# Tractive_System_Board_Rev4.net
KiCad netlist of a schematic drawn in EAGLE
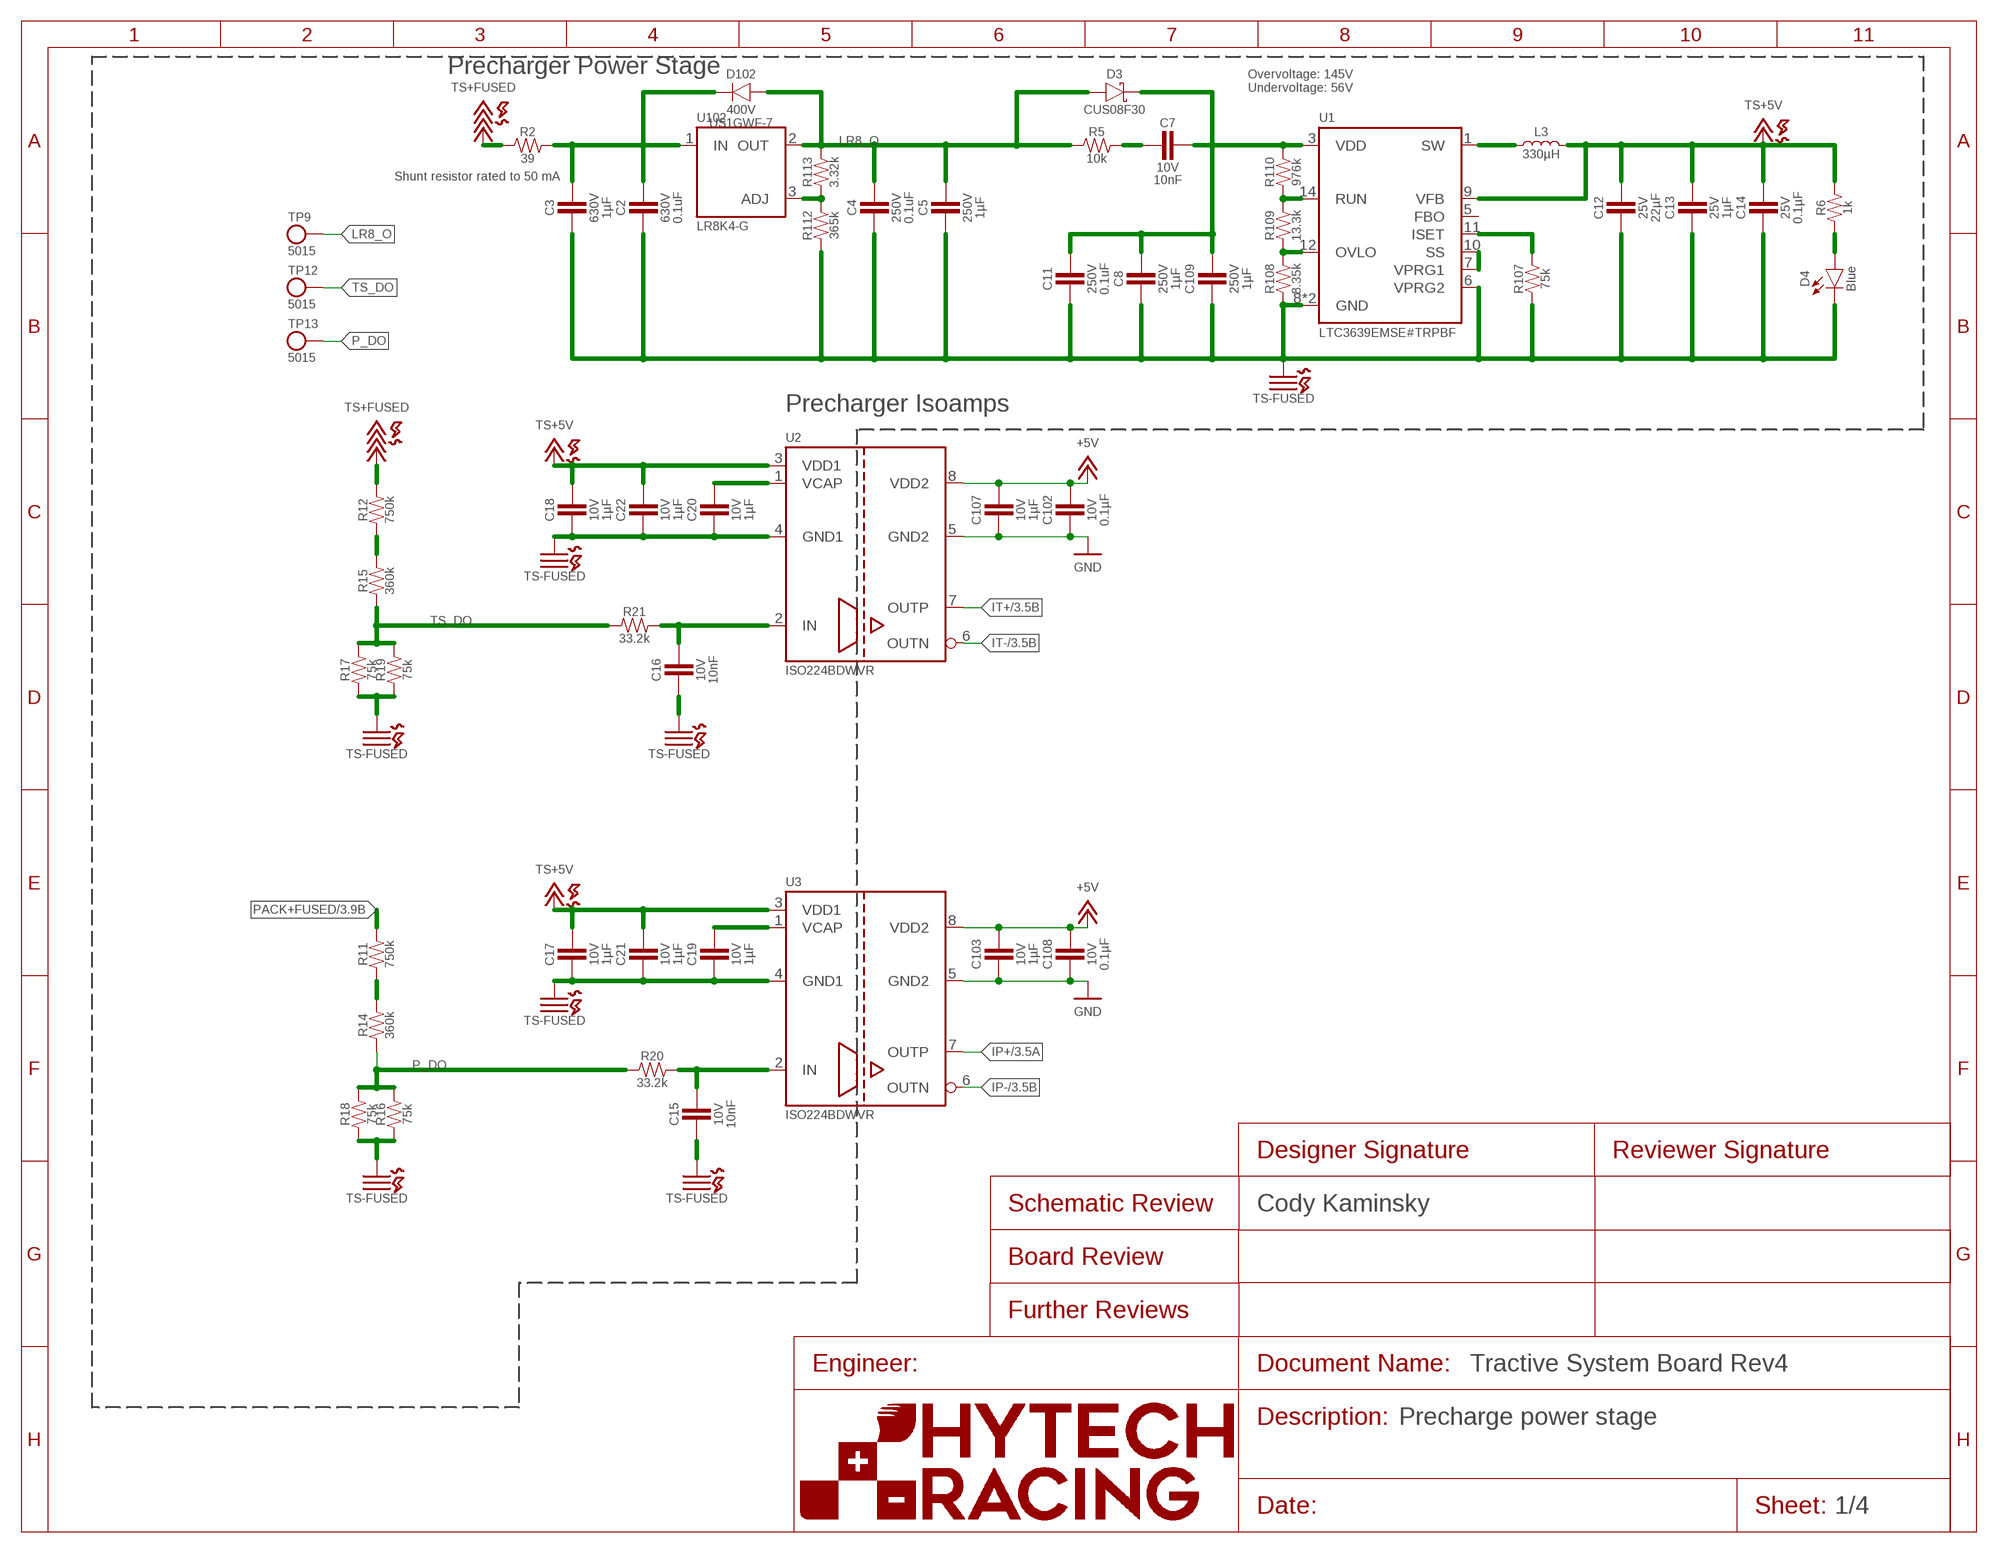
[diagram p0: schematic, sheet 1]
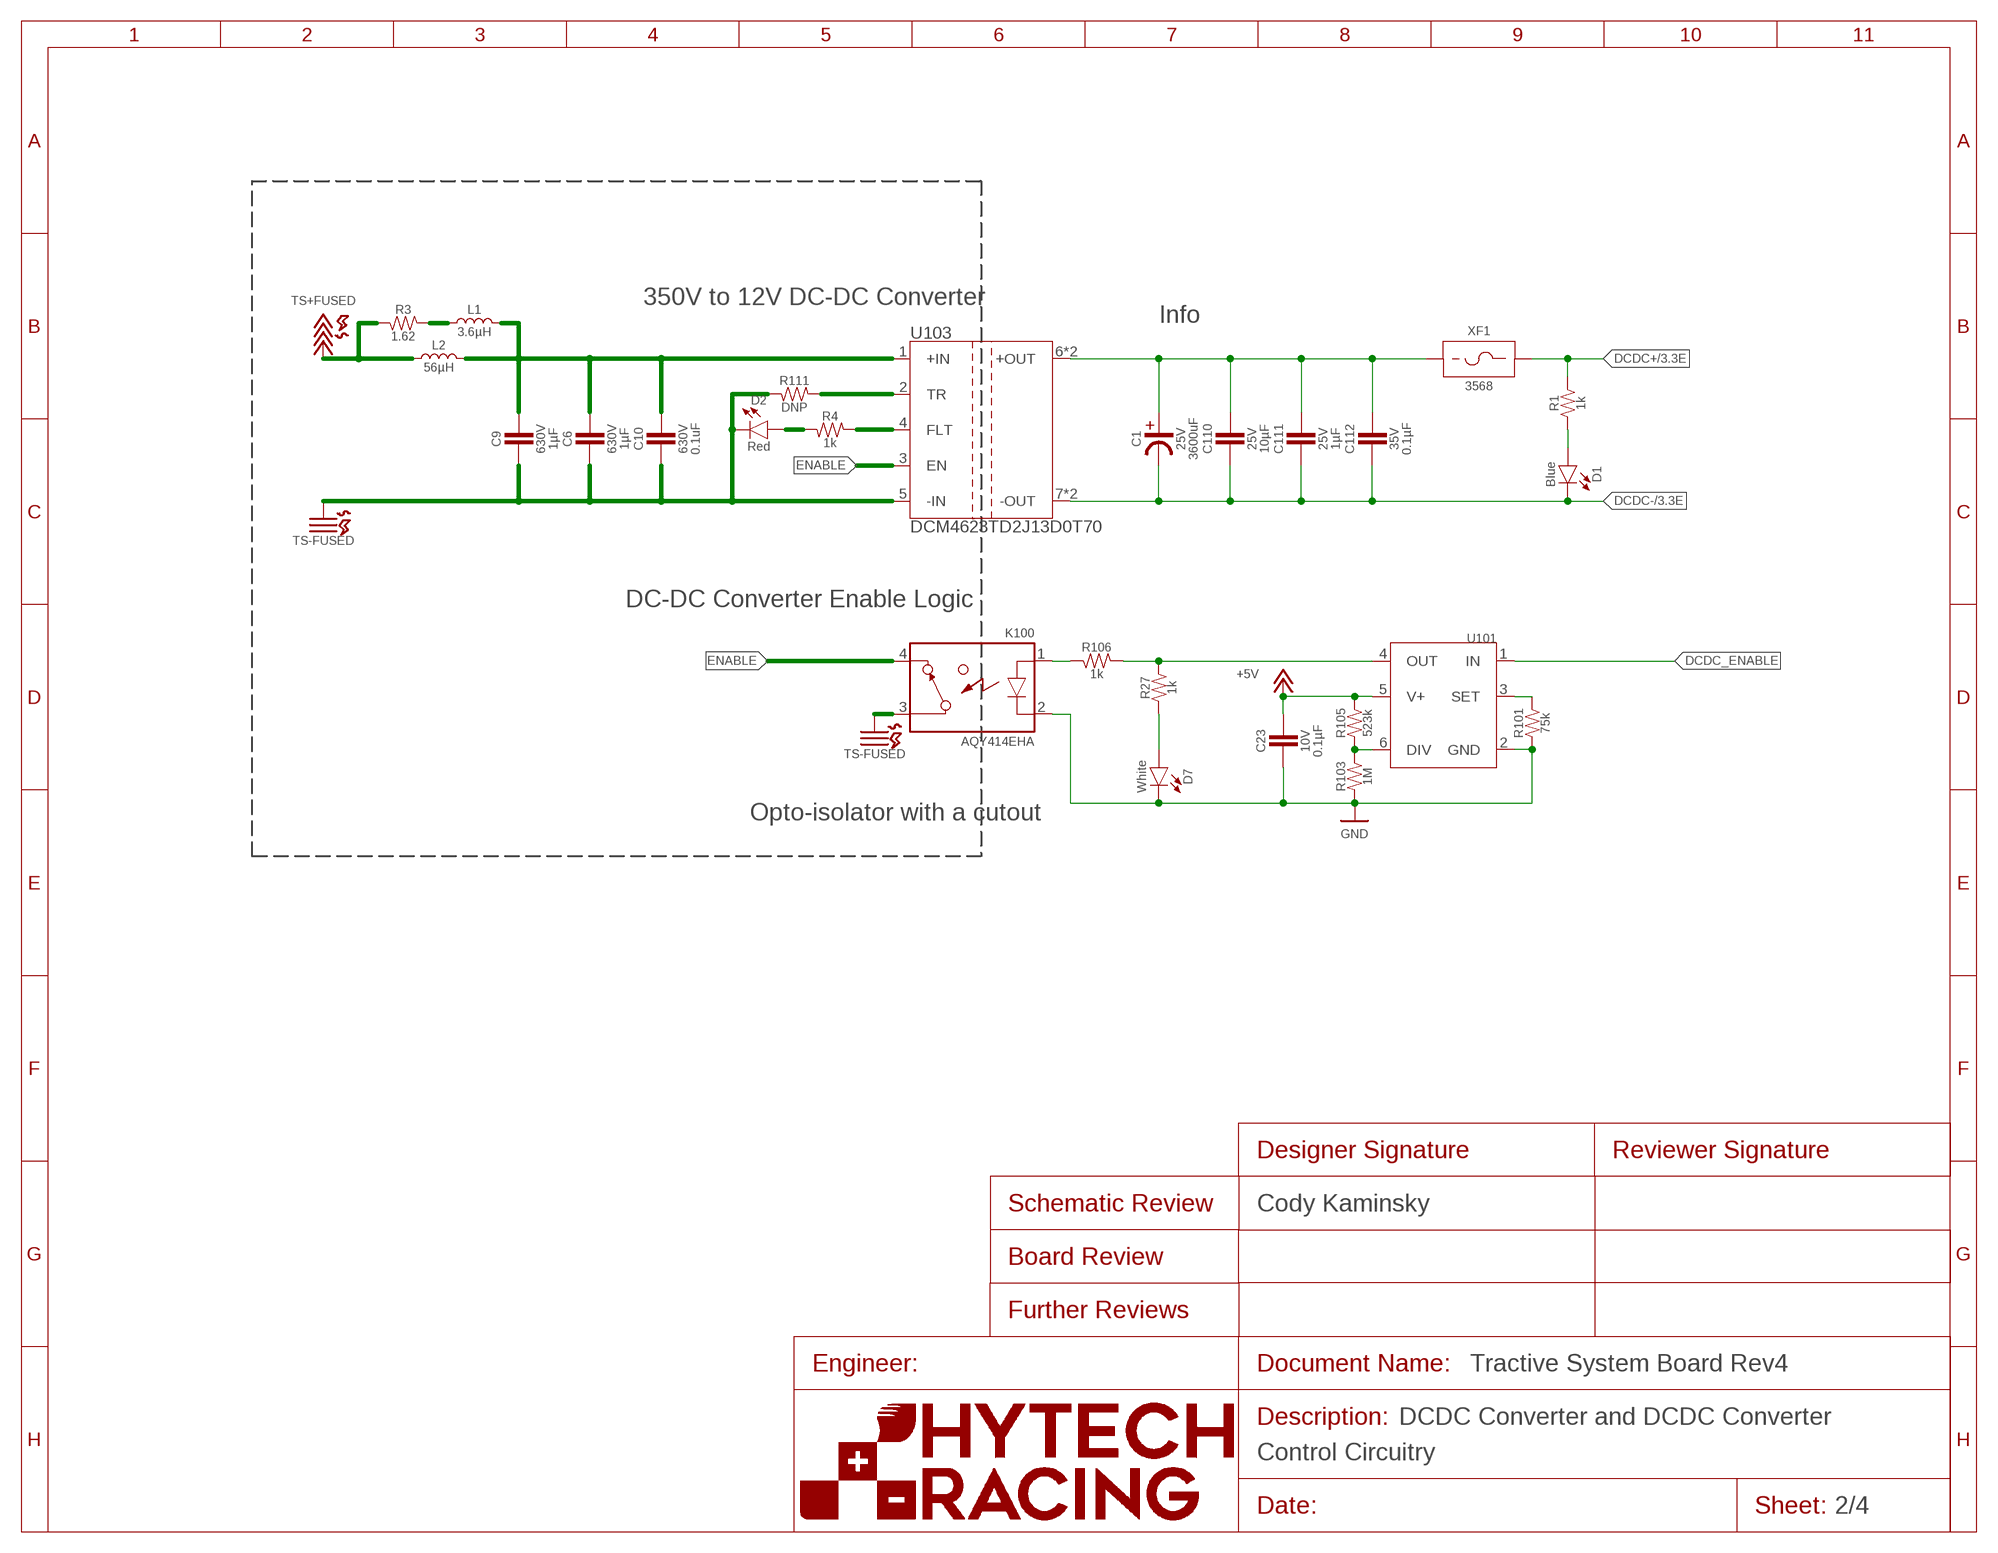
[diagram p1: schematic, sheet 2]
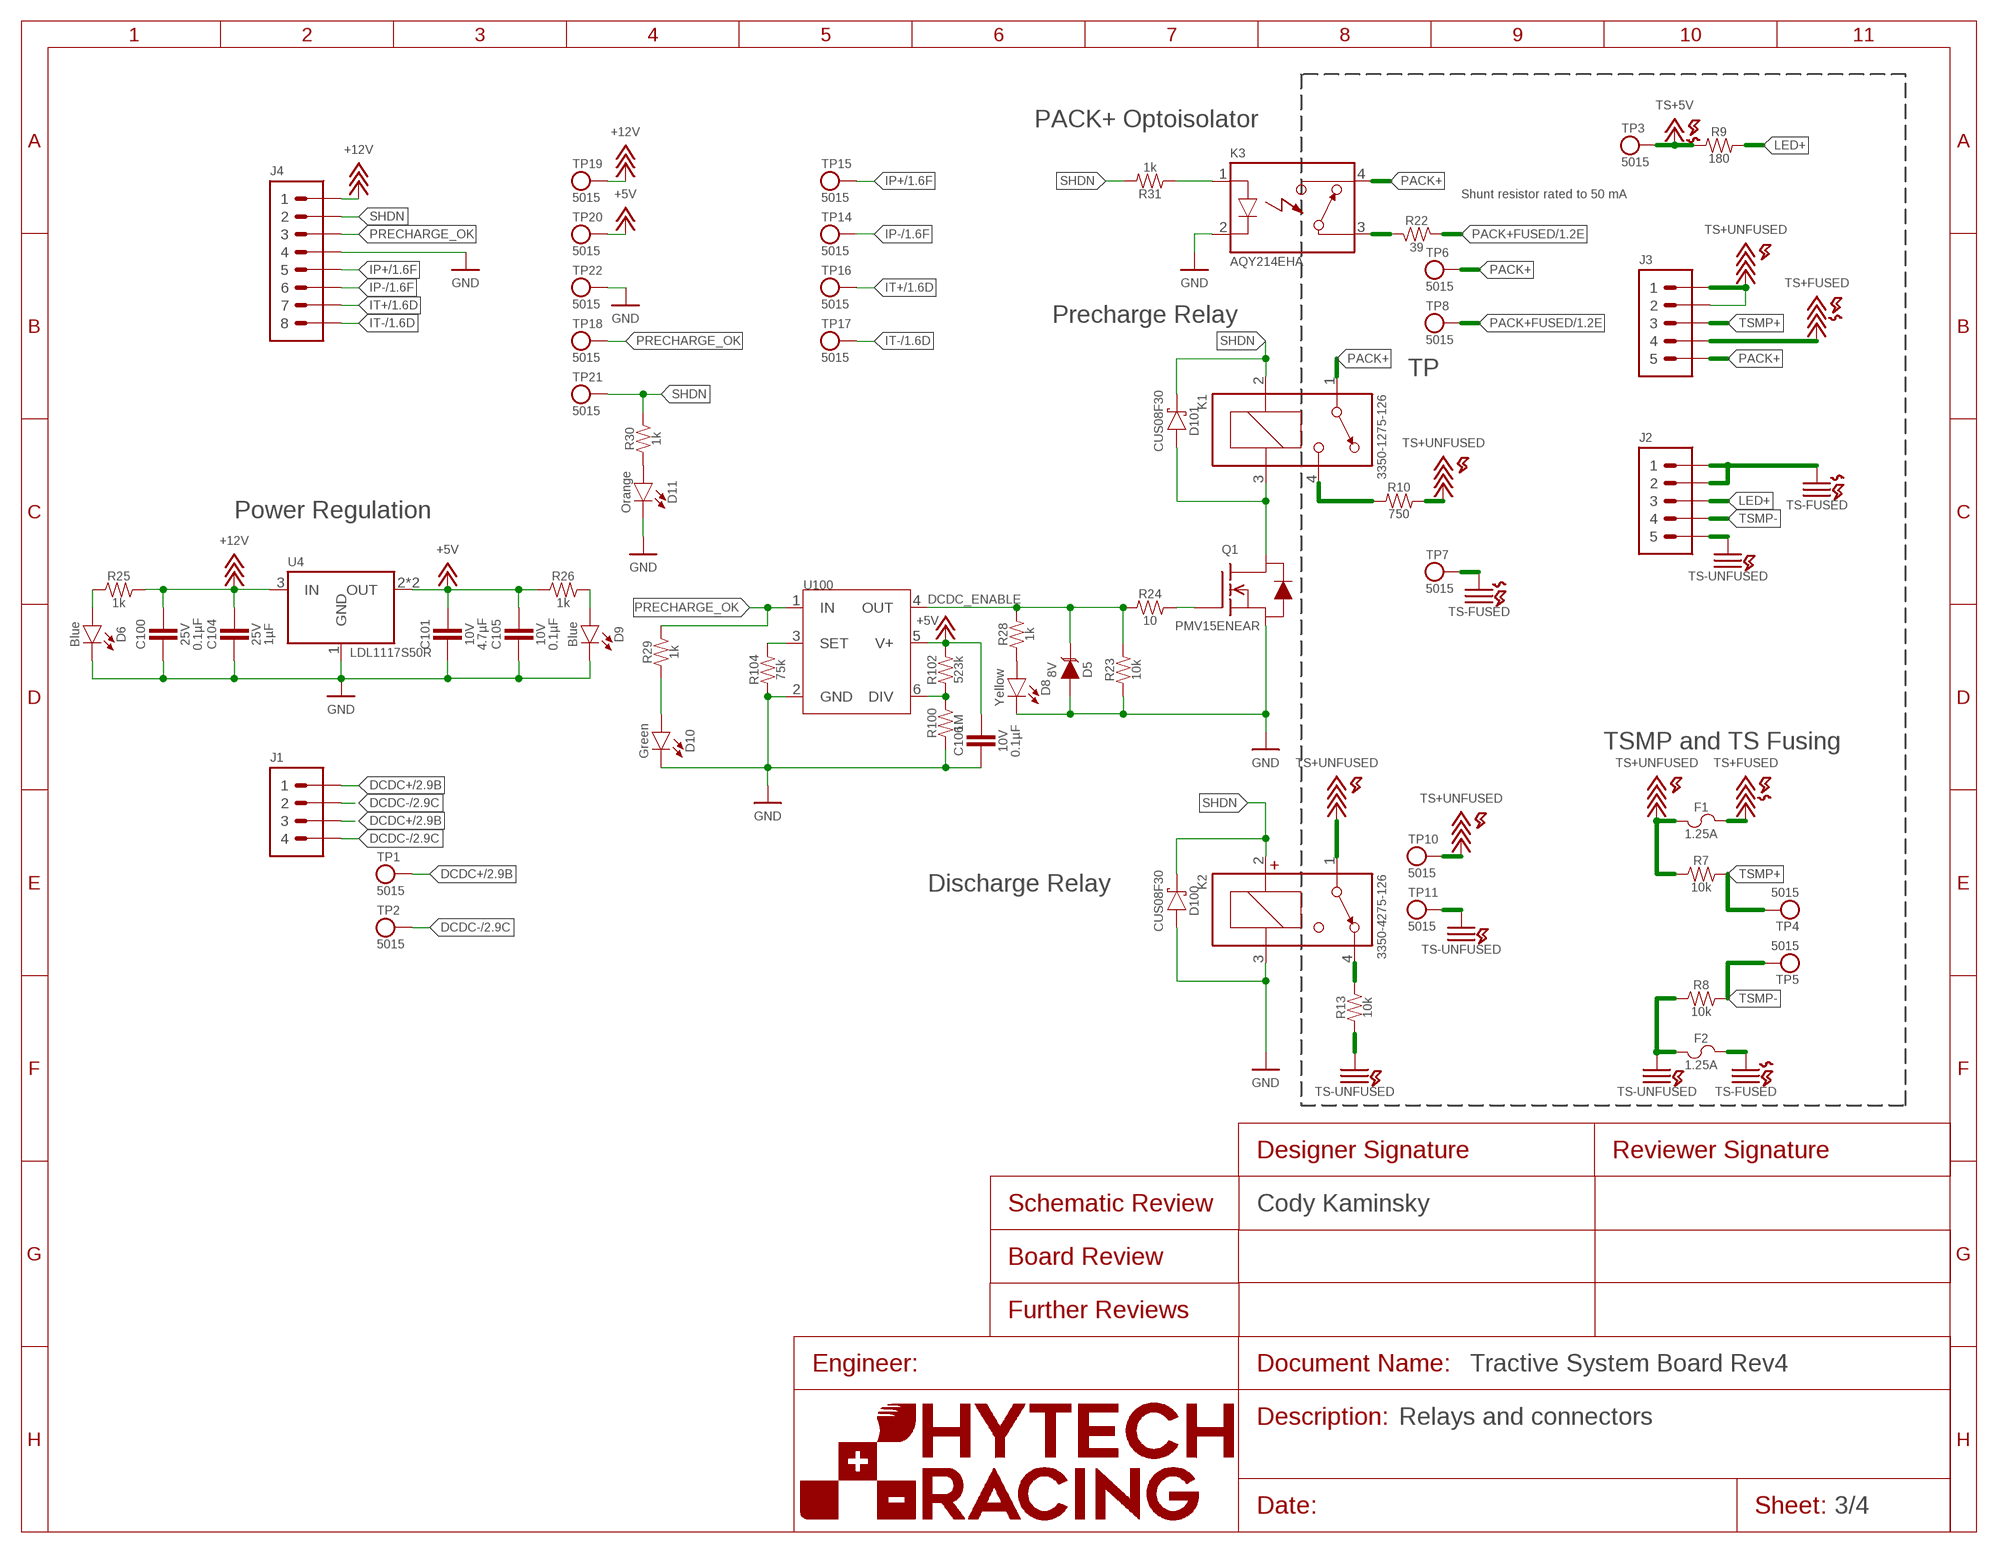
[diagram p2: schematic, sheet 3]
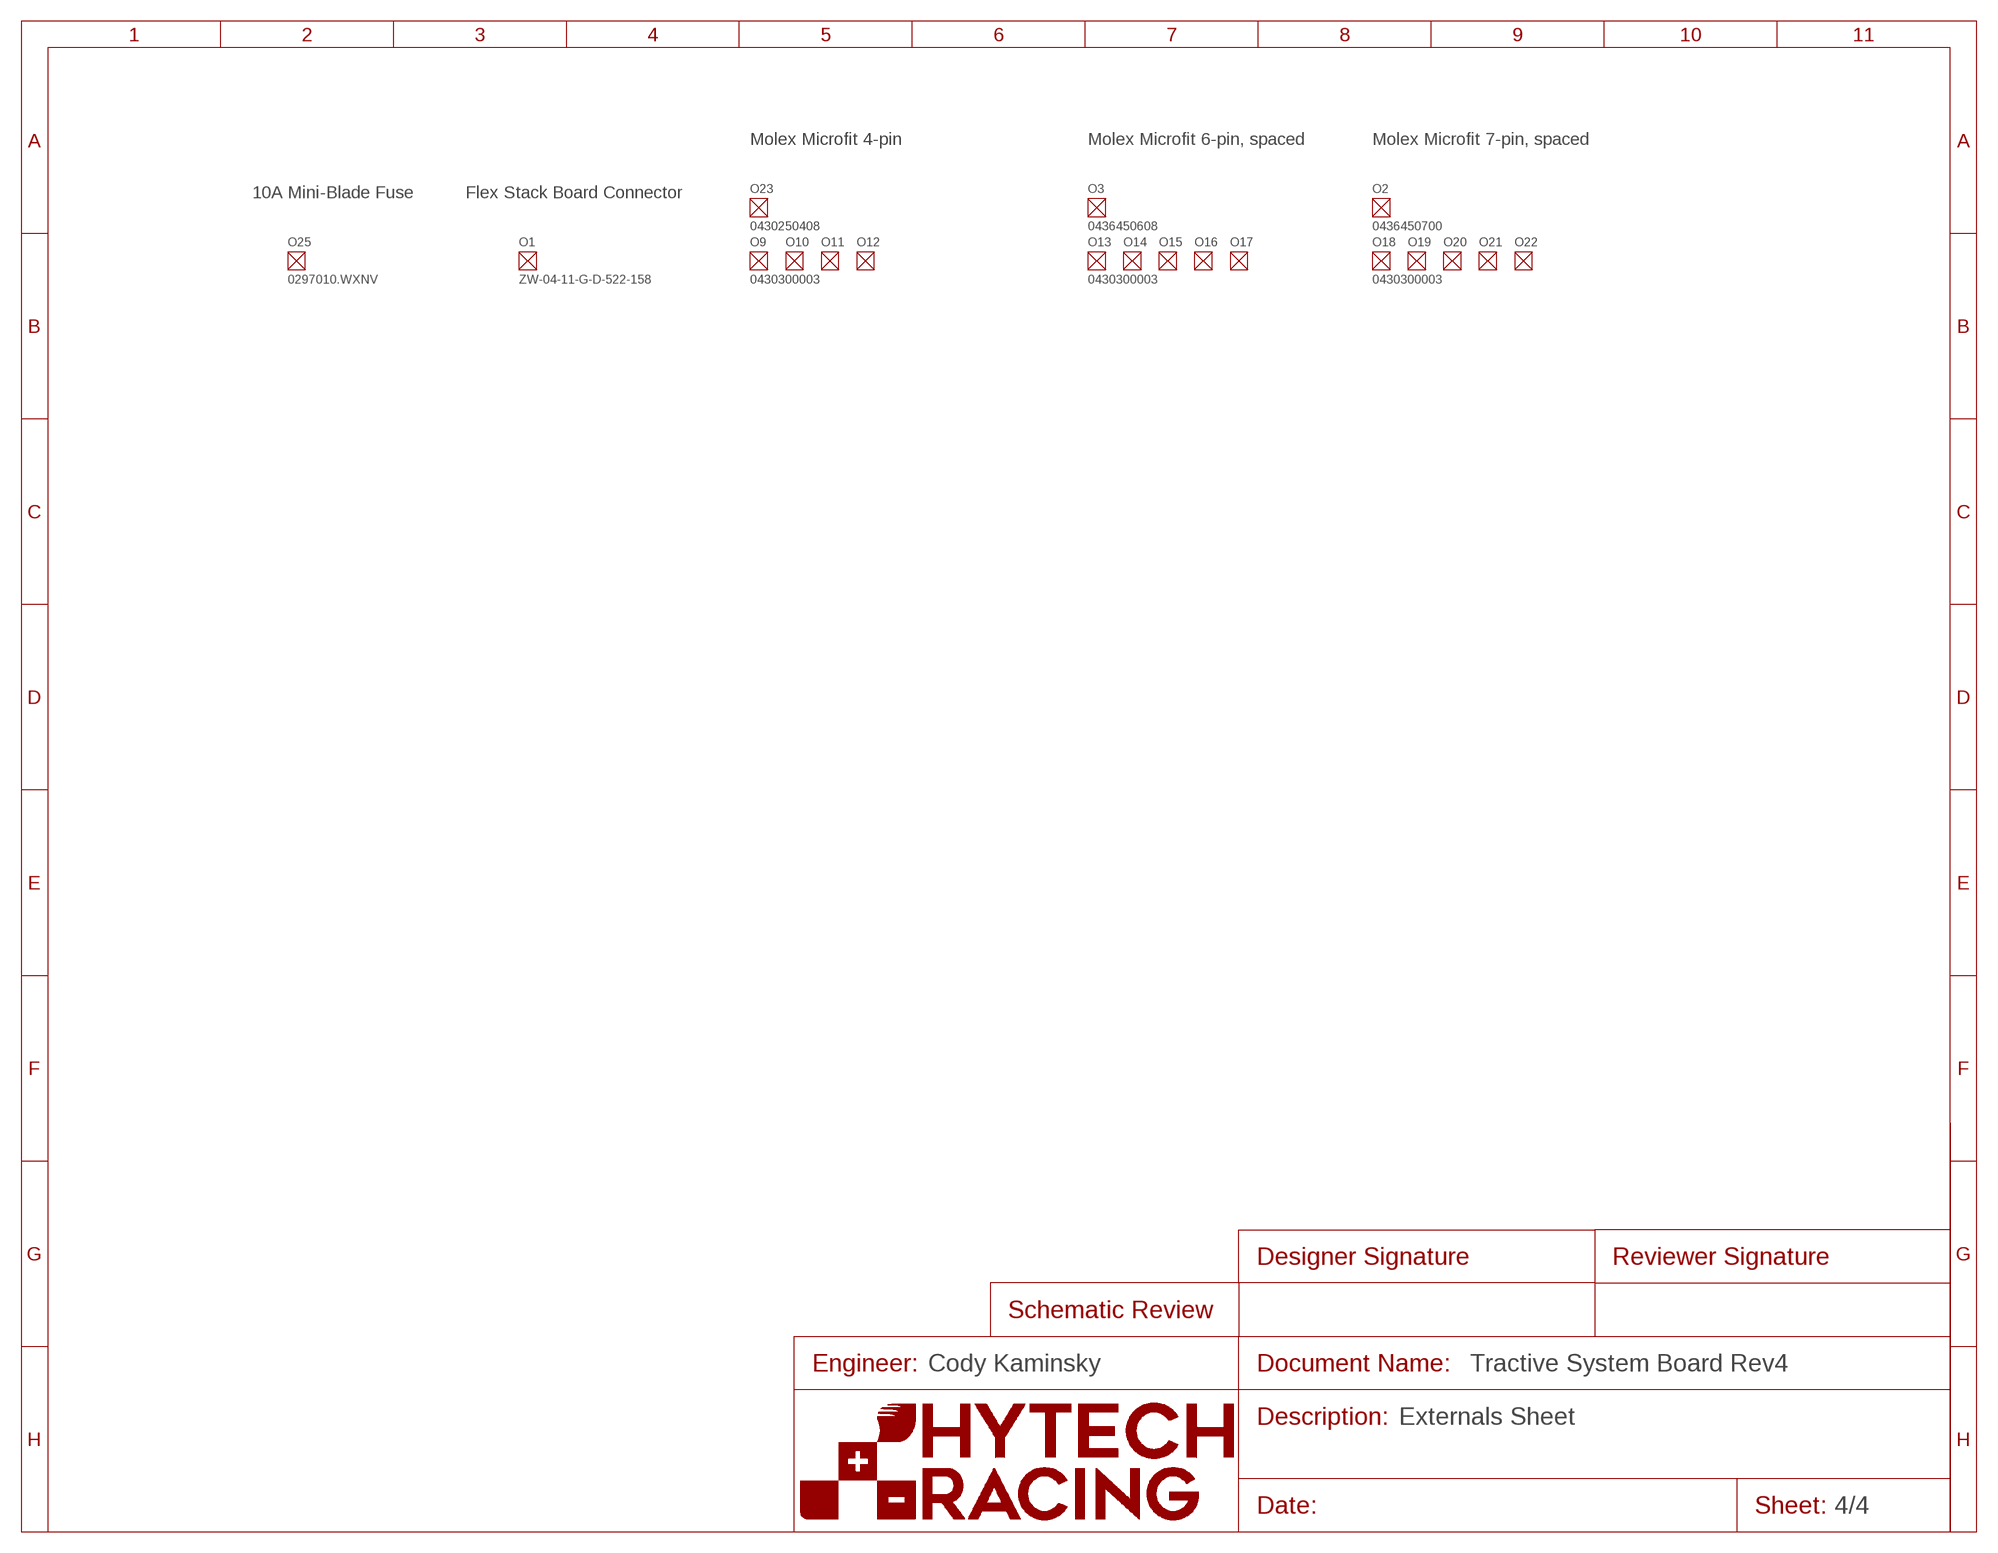
[diagram p3: schematic, sheet 4]

(export (version "E")
  (design (tool "Eeschema 10.0.6"))
  (components
    (comp (ref "C100")
      (value "CAPACITOR_0603_25V_0.1UF")
      (footprint "eagle-import:0603-CAP")
      (fields
        (field (name "CAPACITANCE") "0.1µF")
        (field (name "MANUFACTURER") "Samsung Electro-Mechanics")
        (field (name "MPN") "CL10B104KA8NNNC")
        (field (name "TOLERANCE") "10%")
        (field (name "VOLTAGE") "25V")
      )
      (libsource (lib "eagle-import") (part "CAPACITOR_?_060325V_0.1UF"))
    )
    (comp (ref "C101")
      (value "CAPACITOR_0603_10V_4.7UF")
      (footprint "eagle-import:0603-CAP")
      (fields
        (field (name "CAPACITANCE") "4.7µF")
        (field (name "MANUFACTURER") "Samsung Electro-Mechanics")
        (field (name "MPN") "CL10A475KP8NNNC")
        (field (name "TOLERANCE") "10%")
        (field (name "VOLTAGE") "10V")
      )
      (libsource (lib "eagle-import") (part "CAPACITOR_?_060310V_4.7UF"))
    )
    (comp (ref "C104")
      (value "CAPACITOR_0603_25V_1UF")
      (footprint "eagle-import:0603-CAP")
      (fields
        (field (name "CAPACITANCE") "1µF")
        (field (name "MANUFACTURER") "Samsung Electro-Mechanics")
        (field (name "MPN") "CL10B105KA8NNNC")
        (field (name "TOLERANCE") "10%")
        (field (name "VOLTAGE") "25V")
      )
      (libsource (lib "eagle-import") (part "CAPACITOR_?_060325V_1UF"))
    )
    (comp (ref "C105")
      (value "CAPACITOR_0603_10V_0.1UF")
      (footprint "eagle-import:0603-CAP")
      (fields
        (field (name "CAPACITANCE") "0.1µF")
        (field (name "MANUFACTURER") "Vishay Vitramon")
        (field (name "MPN") "VJ0603Y104JXQPW1BC")
        (field (name "TOLERANCE") "5%")
        (field (name "VOLTAGE") "10V")
      )
      (libsource (lib "eagle-import") (part "CAPACITOR_?_060310V_0.1UF"))
    )
    (comp (ref "C106")
      (value "CAPACITOR_0603_10V_0.1UF")
      (footprint "eagle-import:0603-CAP")
      (fields
        (field (name "CAPACITANCE") "0.1µF")
        (field (name "MANUFACTURER") "Vishay Vitramon")
        (field (name "MPN") "VJ0603Y104JXQPW1BC")
        (field (name "TOLERANCE") "5%")
        (field (name "VOLTAGE") "10V")
      )
      (libsource (lib "eagle-import") (part "CAPACITOR_?_060310V_0.1UF"))
    )
    (comp (ref "D5")
      (value "TVS_8V")
      (footprint "eagle-import:SOT-23")
      (fields
        (field (name "MANUFACTURER") "Vishay General Semiconductor - Diodes Division")
        (field (name "MPN") "GSOT08-E3-08")
        (field (name "VOLTAGE") "8V")
      )
      (libsource (lib "eagle-import") (part "TVS_8V"))
    )
    (comp (ref "D6")
      (value "LED_0603_BLUE")
      (footprint "eagle-import:0603-LED")
      (fields
        (field (name "COLOR") "Blue")
        (field (name "MANUFACTURER") "Kingbright")
        (field (name "MPN") "APT1608VBC/D")
      )
      (libsource (lib "eagle-import") (part "LED_?_0603BLUE"))
    )
    (comp (ref "D8")
      (value "LED_0603_YELLOW")
      (footprint "eagle-import:0603-LED")
      (fields
        (field (name "COLOR") "Yellow")
        (field (name "MANUFACTURER") "Kingbright")
        (field (name "MPN") "APT1608SYCK/J3-PRV")
      )
      (libsource (lib "eagle-import") (part "LED_?_0603YELLOW"))
    )
    (comp (ref "D9")
      (value "LED_0603_BLUE")
      (footprint "eagle-import:0603-LED")
      (fields
        (field (name "COLOR") "Blue")
        (field (name "MANUFACTURER") "Kingbright")
        (field (name "MPN") "APT1608VBC/D")
      )
      (libsource (lib "eagle-import") (part "LED_?_0603BLUE"))
    )
    (comp (ref "D10")
      (value "LED_0603_GREEN")
      (footprint "eagle-import:0603-LED")
      (fields
        (field (name "COLOR") "Green")
        (field (name "MANUFACTURER") "Kingbright")
        (field (name "MPN") "APT1608ZGCK")
      )
      (libsource (lib "eagle-import") (part "LED_?_0603GREEN"))
    )
    (comp (ref "D11")
      (value "LED_0603_ORANGE")
      (footprint "eagle-import:0603-LED")
      (fields
        (field (name "COLOR") "Orange")
        (field (name "MANUFACTURER") "Kingbright")
        (field (name "MPN") "APT1608SECK")
      )
      (libsource (lib "eagle-import") (part "LED_?_0603ORANGE"))
    )
    (comp (ref "D100")
      (value "SCHOTTKY_SOD323_30V")
      (footprint "eagle-import:SOD-323")
      (fields
        (field (name "MANUFACTURER") "Toshiba Semiconductor and Storage")
        (field (name "MPN") "CUS08F30")
        (field (name "VOLTAGE") "30V")
      )
      (libsource (lib "eagle-import") (part "SCHOTTKY_?_SOD32330V"))
    )
    (comp (ref "D101")
      (value "SCHOTTKY_SOD323_30V")
      (footprint "eagle-import:SOD-323")
      (fields
        (field (name "MANUFACTURER") "Toshiba Semiconductor and Storage")
        (field (name "MPN") "CUS08F30")
        (field (name "VOLTAGE") "30V")
      )
      (libsource (lib "eagle-import") (part "SCHOTTKY_?_SOD32330V"))
    )
    (comp (ref "F1")
      (value "FUSE_0885_1.25")
      (footprint "eagle-import:0885")
      (fields
        (field (name "CURRENT") "1.25A")
        (field (name "MANUFACTURER") "Littelfuse Inc.")
        (field (name "MPN") "08851.25DR")
        (field (name "VOLTAGE") "500V")
      )
      (libsource (lib "eagle-import") (part "FUSE_?_08851.25"))
    )
    (comp (ref "F2")
      (value "FUSE_0885_1.25")
      (footprint "eagle-import:0885")
      (fields
        (field (name "CURRENT") "1.25A")
        (field (name "MANUFACTURER") "Littelfuse Inc.")
        (field (name "MPN") "08851.25DR")
        (field (name "VOLTAGE") "500V")
      )
      (libsource (lib "eagle-import") (part "FUSE_?_08851.25"))
    )
    (comp (ref "J1")
      (value "CONNECTOR-4__")
      (footprint "eagle-import:MOLEX_MICROFIT_PTH_VERTICAL_04_DUAL")
      (fields (field (name "MPN") "2068320423") (field (name "MANUFACTURER") "Molex"))
      (libsource (lib "eagle-import") (part "CONNECTOR-4_?_"))
    )
    (comp (ref "J2")
      (value "CONNECTOR-5_MICRO_V6S_")
      (footprint "eagle-import:MOLEX_MICROFIT_PTH_VERTICAL_06_SINGLE_SPACED")
      (fields (field (name "MPN") "2165713006") (field (name "MANUFACTURER") "Molex"))
      (libsource (lib "eagle-import") (part "CONNECTOR-5_?_MICRO_V6S"))
    )
    (comp (ref "J3")
      (value "CONNECTOR-5_MICRO_V7S_")
      (footprint "eagle-import:MOLEX_MICROFIT_PTH_VERTICAL_07_SINGLE_SPACED")
      (fields (field (name "MPN") "2165713007") (field (name "MANUFACTURER") "Molex"))
      (libsource (lib "eagle-import") (part "CONNECTOR-5_?_MICRO_V7S"))
    )
    (comp (ref "J4")
      (value "CONNECTOR-8_S_S")
      (footprint "eagle-import:FLEX_STACK_PTH_08_DUAL")
      (fields
        (field (name "MANUFACTURER") "Sullins Connector Solutions")
        (field (name "MPN") "PPPC042LFBN-RC")
      )
      (libsource (lib "eagle-import") (part "CONNECTOR-8_?_SS"))
    )
    (comp (ref "K1")
      (value "RELAY_SPST_NO_3550_12")
      (footprint "eagle-import:335X")
      (fields (field (name "MANUFACTURER") "Comus International") (field (name "MPN") "3350-1275-126"))
      (libsource (lib "eagle-import") (part "RELAY_SPST_NO_?3550_12"))
    )
    (comp (ref "K2")
      (value "RELAY_SPST_NC_POLARIZED_3550_12")
      (footprint "eagle-import:335X")
      (fields (field (name "MANUFACTURER") "Comus International") (field (name "MPN") "3350-4275-126"))
      (libsource (lib "eagle-import") (part "RELAY_SPST_NC_POLARIZED_?3550_12"))
    )
    (comp (ref "K3")
      (value "RELAY_SOLIDSTATE_NO_AG")
      (footprint "eagle-import:DIP-4_AIRGAP")
      (fields (field (name "MPN") "AQY214EHA") (field (name "MANUFACTURER") "Panasonic Inustrial Devices"))
      (libsource (lib "eagle-import") (part "RELAY_SOLIDSTATE_NO_AG"))
    )
    (comp (ref "Q1")
      (value "TRANSISTOR_N_MOS__PMV15ENEA")
      (footprint "eagle-import:SOT-23")
      (fields (field (name "MANUFACTURER") "Nexperia USA Inc.") (field (name "MPN") "PMV15ENEAR"))
      (libsource (lib "eagle-import") (part "TRANSISTOR_N_MOS_?_PMV15ENEA"))
    )
    (comp (ref "R7")
      (value "RESISTOR_B20_10K")
      (footprint "eagle-import:B20")
      (fields
        (field (name "MANUFACTURER") "Ohmite")
        (field (name "MPN") "B20J10KE")
        (field (name "POWER") "20W")
        (field (name "RESISTANCE") "10k")
      )
      (libsource (lib "eagle-import") (part "RESISTOR_?_B2010K"))
    )
    (comp (ref "R8")
      (value "RESISTOR_B20_10K")
      (footprint "eagle-import:B20")
      (fields
        (field (name "MANUFACTURER") "Ohmite")
        (field (name "MPN") "B20J10KE")
        (field (name "POWER") "20W")
        (field (name "RESISTANCE") "10k")
      )
      (libsource (lib "eagle-import") (part "RESISTOR_?_B2010K"))
    )
    (comp (ref "R9")
      (value "RESISTOR_0603_180")
      (footprint "eagle-import:0603-RES")
      (fields
        (field (name "MANUFACTURER") "Yageo")
        (field (name "MPN") "RC0603FR-07180RL")
        (field (name "POWER") "0.1W")
        (field (name "RESISTANCE") "180")
      )
      (libsource (lib "eagle-import") (part "RESISTOR_?_0603180"))
    )
    (comp (ref "R10")
      (value "RESISTOR_B20_750")
      (footprint "eagle-import:B20")
      (fields
        (field (name "MANUFACTURER") "Ohmite")
        (field (name "MPN") "B20J750E")
        (field (name "POWER") "20W")
        (field (name "RESISTANCE") "750")
      )
      (libsource (lib "eagle-import") (part "RESISTOR_?_B20750"))
    )
    (comp (ref "R13")
      (value "RESISTOR_B20_10K")
      (footprint "eagle-import:B20")
      (fields
        (field (name "MANUFACTURER") "Ohmite")
        (field (name "MPN") "B20J10KE")
        (field (name "POWER") "20W")
        (field (name "RESISTANCE") "10k")
      )
      (libsource (lib "eagle-import") (part "RESISTOR_?_B2010K"))
    )
    (comp (ref "R22")
      (value "RESISTOR_0603_39")
      (footprint "eagle-import:0603-RES")
      (fields
        (field (name "MANUFACTURER") "Yageo")
        (field (name "MPN") "RT0603BRD0739RL")
        (field (name "POWER") "0.1W")
        (field (name "RESISTANCE") "39")
      )
      (libsource (lib "eagle-import") (part "RESISTOR_?_060339"))
    )
    (comp (ref "R23")
      (value "RESISTOR_0603_10K")
      (footprint "eagle-import:0603-RES")
      (fields
        (field (name "MANUFACTURER") "Yageo")
        (field (name "MPN") "RC0603FR-0710KL")
        (field (name "POWER") "0.1W")
        (field (name "RESISTANCE") "10k")
      )
      (libsource (lib "eagle-import") (part "RESISTOR_?_060310K"))
    )
    (comp (ref "R24")
      (value "RESISTOR_0603_10")
      (footprint "eagle-import:0603-RES")
      (fields
        (field (name "MANUFACTURER") "Yageo")
        (field (name "MPN") "RC0603FR-0710RL")
        (field (name "POWER") "0.1W")
        (field (name "RESISTANCE") "10")
      )
      (libsource (lib "eagle-import") (part "RESISTOR_?_060310"))
    )
    (comp (ref "R25")
      (value "RESISTOR_0603_1K")
      (footprint "eagle-import:0603-RES")
      (fields
        (field (name "MANUFACTURER") "Yageo")
        (field (name "MPN") "RC0603FR-071KL")
        (field (name "POWER") "0.1W")
        (field (name "RESISTANCE") "1k")
      )
      (libsource (lib "eagle-import") (part "RESISTOR_?_06031K"))
    )
    (comp (ref "R26")
      (value "RESISTOR_0603_1K")
      (footprint "eagle-import:0603-RES")
      (fields
        (field (name "MANUFACTURER") "Yageo")
        (field (name "MPN") "RC0603FR-071KL")
        (field (name "POWER") "0.1W")
        (field (name "RESISTANCE") "1k")
      )
      (libsource (lib "eagle-import") (part "RESISTOR_?_06031K"))
    )
    (comp (ref "R28")
      (value "RESISTOR_0603_1K")
      (footprint "eagle-import:0603-RES")
      (fields
        (field (name "MANUFACTURER") "Yageo")
        (field (name "MPN") "RC0603FR-071KL")
        (field (name "POWER") "0.1W")
        (field (name "RESISTANCE") "1k")
      )
      (libsource (lib "eagle-import") (part "RESISTOR_?_06031K"))
    )
    (comp (ref "R29")
      (value "RESISTOR_0603_1K")
      (footprint "eagle-import:0603-RES")
      (fields
        (field (name "MANUFACTURER") "Yageo")
        (field (name "MPN") "RC0603FR-071KL")
        (field (name "POWER") "0.1W")
        (field (name "RESISTANCE") "1k")
      )
      (libsource (lib "eagle-import") (part "RESISTOR_?_06031K"))
    )
    (comp (ref "R30")
      (value "RESISTOR_0603_1K")
      (footprint "eagle-import:0603-RES")
      (fields
        (field (name "MANUFACTURER") "Yageo")
        (field (name "MPN") "RC0603FR-071KL")
        (field (name "POWER") "0.1W")
        (field (name "RESISTANCE") "1k")
      )
      (libsource (lib "eagle-import") (part "RESISTOR_?_06031K"))
    )
    (comp (ref "R31")
      (value "RESISTOR_0603_1K")
      (footprint "eagle-import:0603-RES")
      (fields
        (field (name "MANUFACTURER") "Yageo")
        (field (name "MPN") "RC0603FR-071KL")
        (field (name "POWER") "0.1W")
        (field (name "RESISTANCE") "1k")
      )
      (libsource (lib "eagle-import") (part "RESISTOR_?_06031K"))
    )
    (comp (ref "R100")
      (value "RESISTOR_0805_1M")
      (footprint "eagle-import:0805-RES")
      (fields
        (field (name "MANUFACTURER") "Panasonic Electronic Components")
        (field (name "MPN") "ERJ-PB6B1004V")
        (field (name "POWER") "0.25W")
        (field (name "RESISTANCE") "1M")
      )
      (libsource (lib "eagle-import") (part "RESISTOR_?_08051M"))
    )
    (comp (ref "R102")
      (value "RESISTOR_0805_523K")
      (footprint "eagle-import:0805-RES")
      (fields
        (field (name "MANUFACTURER") "Panasonic Electronic Components")
        (field (name "MPN") "ERJ-PB6B5233V")
        (field (name "POWER") "0.25W")
        (field (name "RESISTANCE") "523k")
      )
      (libsource (lib "eagle-import") (part "RESISTOR_?_0805523K"))
    )
    (comp (ref "R104")
      (value "RESISTOR_0603_75K")
      (footprint "eagle-import:0603-RES")
      (fields
        (field (name "MANUFACTURER") "Yageo")
        (field (name "MPN") "RT0603BRE0775KL")
        (field (name "POWER") "0.1W")
        (field (name "RESISTANCE") "75k")
      )
      (libsource (lib "eagle-import") (part "RESISTOR_?_060375K"))
    )
    (comp (ref "TP1")
      (value "TEST_POINT")
      (footprint "eagle-import:MICRO_MINIATURE")
      (fields (field (name "MPN") "5015") (field (name "MANUFACTURER") "Keystone Electronics"))
      (libsource (lib "eagle-import") (part "TEST_POINT"))
    )
    (comp (ref "TP2")
      (value "TEST_POINT")
      (footprint "eagle-import:MICRO_MINIATURE")
      (fields (field (name "MPN") "5015") (field (name "MANUFACTURER") "Keystone Electronics"))
      (libsource (lib "eagle-import") (part "TEST_POINT"))
    )
    (comp (ref "TP3")
      (value "TEST_POINT")
      (footprint "eagle-import:MICRO_MINIATURE")
      (fields (field (name "MPN") "5015") (field (name "MANUFACTURER") "Keystone Electronics"))
      (libsource (lib "eagle-import") (part "TEST_POINT"))
    )
    (comp (ref "TP4")
      (value "TEST_POINT")
      (footprint "eagle-import:MICRO_MINIATURE")
      (fields (field (name "MPN") "5015") (field (name "MANUFACTURER") "Keystone Electronics"))
      (libsource (lib "eagle-import") (part "TEST_POINT"))
    )
    (comp (ref "TP5")
      (value "TEST_POINT")
      (footprint "eagle-import:MICRO_MINIATURE")
      (fields (field (name "MPN") "5015") (field (name "MANUFACTURER") "Keystone Electronics"))
      (libsource (lib "eagle-import") (part "TEST_POINT"))
    )
    (comp (ref "TP6")
      (value "TEST_POINT")
      (footprint "eagle-import:MICRO_MINIATURE")
      (fields (field (name "MPN") "5015") (field (name "MANUFACTURER") "Keystone Electronics"))
      (libsource (lib "eagle-import") (part "TEST_POINT"))
    )
    (comp (ref "TP7")
      (value "TEST_POINT")
      (footprint "eagle-import:MICRO_MINIATURE")
      (fields (field (name "MPN") "5015") (field (name "MANUFACTURER") "Keystone Electronics"))
      (libsource (lib "eagle-import") (part "TEST_POINT"))
    )
    (comp (ref "TP8")
      (value "TEST_POINT")
      (footprint "eagle-import:MICRO_MINIATURE")
      (fields (field (name "MPN") "5015") (field (name "MANUFACTURER") "Keystone Electronics"))
      (libsource (lib "eagle-import") (part "TEST_POINT"))
    )
    (comp (ref "TP10")
      (value "TEST_POINT")
      (footprint "eagle-import:MICRO_MINIATURE")
      (fields (field (name "MPN") "5015") (field (name "MANUFACTURER") "Keystone Electronics"))
      (libsource (lib "eagle-import") (part "TEST_POINT"))
    )
    (comp (ref "TP11")
      (value "TEST_POINT")
      (footprint "eagle-import:MICRO_MINIATURE")
      (fields (field (name "MPN") "5015") (field (name "MANUFACTURER") "Keystone Electronics"))
      (libsource (lib "eagle-import") (part "TEST_POINT"))
    )
    (comp (ref "TP14")
      (value "TEST_POINT")
      (footprint "eagle-import:MICRO_MINIATURE")
      (fields (field (name "MPN") "5015") (field (name "MANUFACTURER") "Keystone Electronics"))
      (libsource (lib "eagle-import") (part "TEST_POINT"))
    )
    (comp (ref "TP15")
      (value "TEST_POINT")
      (footprint "eagle-import:MICRO_MINIATURE")
      (fields (field (name "MPN") "5015") (field (name "MANUFACTURER") "Keystone Electronics"))
      (libsource (lib "eagle-import") (part "TEST_POINT"))
    )
    (comp (ref "TP16")
      (value "TEST_POINT")
      (footprint "eagle-import:MICRO_MINIATURE")
      (fields (field (name "MPN") "5015") (field (name "MANUFACTURER") "Keystone Electronics"))
      (libsource (lib "eagle-import") (part "TEST_POINT"))
    )
    (comp (ref "TP17")
      (value "TEST_POINT")
      (footprint "eagle-import:MICRO_MINIATURE")
      (fields (field (name "MPN") "5015") (field (name "MANUFACTURER") "Keystone Electronics"))
      (libsource (lib "eagle-import") (part "TEST_POINT"))
    )
    (comp (ref "TP18")
      (value "TEST_POINT")
      (footprint "eagle-import:MICRO_MINIATURE")
      (fields (field (name "MPN") "5015") (field (name "MANUFACTURER") "Keystone Electronics"))
      (libsource (lib "eagle-import") (part "TEST_POINT"))
    )
    (comp (ref "TP19")
      (value "TEST_POINT")
      (footprint "eagle-import:MICRO_MINIATURE")
      (fields (field (name "MPN") "5015") (field (name "MANUFACTURER") "Keystone Electronics"))
      (libsource (lib "eagle-import") (part "TEST_POINT"))
    )
    (comp (ref "TP20")
      (value "TEST_POINT")
      (footprint "eagle-import:MICRO_MINIATURE")
      (fields (field (name "MPN") "5015") (field (name "MANUFACTURER") "Keystone Electronics"))
      (libsource (lib "eagle-import") (part "TEST_POINT"))
    )
    (comp (ref "TP21")
      (value "TEST_POINT")
      (footprint "eagle-import:MICRO_MINIATURE")
      (fields (field (name "MPN") "5015") (field (name "MANUFACTURER") "Keystone Electronics"))
      (libsource (lib "eagle-import") (part "TEST_POINT"))
    )
    (comp (ref "TP22")
      (value "TEST_POINT")
      (footprint "eagle-import:MICRO_MINIATURE")
      (fields (field (name "MPN") "5015") (field (name "MANUFACTURER") "Keystone Electronics"))
      (libsource (lib "eagle-import") (part "TEST_POINT"))
    )
    (comp (ref "U4")
      (value "VOLTAGE_REGULATOR_SOT223_5V")
      (footprint "eagle-import:SOT223")
      (fields (field (name "MANUFACTURER") "STMicroelectronics") (field (name "MPN") "LDL1117S50R"))
      (libsource (lib "eagle-import") (part "VOLTAGE_REGULATOR_?_SOT2235V"))
    )
    (comp (ref "U100")
      (value "LTC6994-2")
      (footprint "eagle-import:SOT-23-6")
      (libsource (lib "eagle-import") (part "LTC6994-2"))
    )
    (comp (ref "C1")
      (value "CAPACITOR_POLAR__3600UF")
      (footprint "eagle-import:EKYC_MM")
      (fields
        (field (name "CAPACITANCE") "3600uF")
        (field (name "MANUFACTURER") "United Chemi-con")
        (field (name "MPN") "EKYC250ELL362ML20S")
        (field (name "VOLTAGE") "25V")
      )
      (libsource (lib "eagle-import") (part "CAPACITOR_POLAR_?_3600UF"))
    )
    (comp (ref "C6")
      (value "CAPACITOR_2220_630V_1UF")
      (footprint "eagle-import:2220-CAP")
      (fields
        (field (name "CAPACITANCE") "1µF")
        (field (name "MANUFACTURER") "Knowles Syfer")
        (field (name "MPN") "2220Y6300105KXTWS2")
        (field (name "TOLERANCE") "10%")
        (field (name "VOLTAGE") "630V")
      )
      (libsource (lib "eagle-import") (part "CAPACITOR_?_2220630V_1UF"))
    )
    (comp (ref "C9")
      (value "CAPACITOR_2220_630V_1UF")
      (footprint "eagle-import:2220-CAP")
      (fields
        (field (name "CAPACITANCE") "1µF")
        (field (name "MANUFACTURER") "Knowles Syfer")
        (field (name "MPN") "2220Y6300105KXTWS2")
        (field (name "TOLERANCE") "10%")
        (field (name "VOLTAGE") "630V")
      )
      (libsource (lib "eagle-import") (part "CAPACITOR_?_2220630V_1UF"))
    )
    (comp (ref "C10")
      (value "CAPACITOR_2220_630V_0.1UF")
      (footprint "eagle-import:2220-CAP")
      (fields
        (field (name "CAPACITANCE") "0.1uF")
        (field (name "MANUFACTURER") "TDK Coporation")
        (field (name "MPN") "C5750CH2J104K280KC")
        (field (name "TOLERANCE") "10%")
        (field (name "VOLTAGE") "630V")
      )
      (libsource (lib "eagle-import") (part "CAPACITOR_?_2220630V_0.1UF"))
    )
    (comp (ref "C23")
      (value "CAPACITOR_0603_10V_0.1UF")
      (footprint "eagle-import:0603-CAP")
      (fields
        (field (name "CAPACITANCE") "0.1µF")
        (field (name "MANUFACTURER") "Vishay Vitramon")
        (field (name "MPN") "VJ0603Y104JXQPW1BC")
        (field (name "TOLERANCE") "5%")
        (field (name "VOLTAGE") "10V")
      )
      (libsource (lib "eagle-import") (part "CAPACITOR_?_060310V_0.1UF"))
    )
    (comp (ref "C110")
      (value "CAPACITOR_0603_25V_10UF")
      (footprint "eagle-import:0603-CAP")
      (fields
        (field (name "CAPACITANCE") "10µF")
        (field (name "MANUFACTURER") "Murata Electronics")
        (field (name "MPN") "GRM188R61E106MA73D")
        (field (name "TOLERANCE") "20%")
        (field (name "VOLTAGE") "25V")
      )
      (libsource (lib "eagle-import") (part "CAPACITOR_?_060325V_10UF"))
    )
    (comp (ref "C111")
      (value "CAPACITOR_0603_25V_1UF")
      (footprint "eagle-import:0603-CAP")
      (fields
        (field (name "CAPACITANCE") "1µF")
        (field (name "MANUFACTURER") "Samsung Electro-Mechanics")
        (field (name "MPN") "CL10B105KA8NNNC")
        (field (name "TOLERANCE") "10%")
        (field (name "VOLTAGE") "25V")
      )
      (libsource (lib "eagle-import") (part "CAPACITOR_?_060325V_1UF"))
    )
    (comp (ref "C112")
      (value "CAPACITOR_0603_35V_0.1UF")
      (footprint "eagle-import:0603-CAP")
      (fields
        (field (name "CAPACITANCE") "0.1µF")
        (field (name "MANUFACTURER") "Taiyo Yuden")
        (field (name "MPN") "GMK107B7104KAHT")
        (field (name "TOLERANCE") "10%")
        (field (name "VOLTAGE") "35V")
      )
      (libsource (lib "eagle-import") (part "CAPACITOR_?_060335V_0.1UF"))
    )
    (comp (ref "D1")
      (value "LED_0603_BLUE")
      (footprint "eagle-import:0603-LED")
      (fields
        (field (name "COLOR") "Blue")
        (field (name "MANUFACTURER") "Kingbright")
        (field (name "MPN") "APT1608VBC/D")
      )
      (libsource (lib "eagle-import") (part "LED_?_0603BLUE"))
    )
    (comp (ref "D2")
      (value "LED_0603_RED")
      (footprint "eagle-import:0603-LED")
      (fields
        (field (name "COLOR") "Red")
        (field (name "MANUFACTURER") "Kingbright")
        (field (name "MPN") "APT1608SECK/J3-PRV")
      )
      (libsource (lib "eagle-import") (part "LED_?_0603RED"))
    )
    (comp (ref "D7")
      (value "LED_0603_WHITE")
      (footprint "eagle-import:0603-LED")
      (fields
        (field (name "COLOR") "White")
        (field (name "MANUFACTURER") "Bivar Inc.")
        (field (name "MPN") "SM0603UWC")
      )
      (libsource (lib "eagle-import") (part "LED_?_0603WHITE"))
    )
    (comp (ref "K100")
      (value "RELAY_SOLIDSTATE_NC_AG")
      (footprint "eagle-import:DIP-4_AIRGAP")
      (fields (field (name "MPN") "AQY414EHA") (field (name "MANUFACTURER") "Panasonic Industrial Devices"))
      (libsource (lib "eagle-import") (part "RELAY_SOLIDSTATE_NC_AG"))
    )
    (comp (ref "L1")
      (value "INDUCTOR_PA4334_3.6UH")
      (footprint "eagle-import:PA4334")
      (fields
        (field (name "INDUCTANCE") "3.6µH")
        (field (name "MANUFACTURER") "Pulse Electonics Company")
        (field (name "MPN") "PA4334.362NLT")
      )
      (libsource (lib "eagle-import") (part "INDUCTOR_?_PA43343.6UH"))
    )
    (comp (ref "L2")
      (value "INDUCTOR_WELMHI_56UH")
      (footprint "eagle-import:WE-LMHI")
      (fields
        (field (name "INDUCTANCE") "56µH")
        (field (name "MANUFACTURER") "Wurth Elektronik")
        (field (name "MPN") "74437349560")
        (field (name "TOLERANCE") "20%")
      )
      (libsource (lib "eagle-import") (part "INDUCTOR_?_WELMHI56UH"))
    )
    (comp (ref "R1")
      (value "RESISTOR_0603_1K")
      (footprint "eagle-import:0603-RES")
      (fields
        (field (name "MANUFACTURER") "Yageo")
        (field (name "MPN") "RC0603FR-071KL")
        (field (name "POWER") "0.1W")
        (field (name "RESISTANCE") "1k")
      )
      (libsource (lib "eagle-import") (part "RESISTOR_?_06031K"))
    )
    (comp (ref "R3")
      (value "RESISTOR_0603_1.62")
      (footprint "eagle-import:0603-RES")
      (fields
        (field (name "MANUFACTURER") "TE Conductivity Passive Product")
        (field (name "MPN") "CPF0603B1R62E1")
        (field (name "POWER") "0.1W")
        (field (name "RESISTANCE") "1.62")
      )
      (libsource (lib "eagle-import") (part "RESISTOR_?_06031.62"))
    )
    (comp (ref "R4")
      (value "RESISTOR_0603_1K")
      (footprint "eagle-import:0603-RES")
      (fields
        (field (name "MANUFACTURER") "Yageo")
        (field (name "MPN") "RC0603FR-071KL")
        (field (name "POWER") "0.1W")
        (field (name "RESISTANCE") "1k")
      )
      (libsource (lib "eagle-import") (part "RESISTOR_?_06031K"))
    )
    (comp (ref "R27")
      (value "RESISTOR_0603_1K")
      (footprint "eagle-import:0603-RES")
      (fields
        (field (name "MANUFACTURER") "Yageo")
        (field (name "MPN") "RC0603FR-071KL")
        (field (name "POWER") "0.1W")
        (field (name "RESISTANCE") "1k")
      )
      (libsource (lib "eagle-import") (part "RESISTOR_?_06031K"))
    )
    (comp (ref "R101")
      (value "RESISTOR_0603_75K")
      (footprint "eagle-import:0603-RES")
      (fields
        (field (name "MANUFACTURER") "Yageo")
        (field (name "MPN") "RT0603BRE0775KL")
        (field (name "POWER") "0.1W")
        (field (name "RESISTANCE") "75k")
      )
      (libsource (lib "eagle-import") (part "RESISTOR_?_060375K"))
    )
    (comp (ref "R103")
      (value "RESISTOR_0805_1M")
      (footprint "eagle-import:0805-RES")
      (fields
        (field (name "MANUFACTURER") "Panasonic Electronic Components")
        (field (name "MPN") "ERJ-PB6B1004V")
        (field (name "POWER") "0.25W")
        (field (name "RESISTANCE") "1M")
      )
      (libsource (lib "eagle-import") (part "RESISTOR_?_08051M"))
    )
    (comp (ref "R105")
      (value "RESISTOR_0805_523K")
      (footprint "eagle-import:0805-RES")
      (fields
        (field (name "MANUFACTURER") "Panasonic Electronic Components")
        (field (name "MPN") "ERJ-PB6B5233V")
        (field (name "POWER") "0.25W")
        (field (name "RESISTANCE") "523k")
      )
      (libsource (lib "eagle-import") (part "RESISTOR_?_0805523K"))
    )
    (comp (ref "R106")
      (value "RESISTOR_0603_1K")
      (footprint "eagle-import:0603-RES")
      (fields
        (field (name "MANUFACTURER") "Yageo")
        (field (name "MPN") "RC0603FR-071KL")
        (field (name "POWER") "0.1W")
        (field (name "RESISTANCE") "1k")
      )
      (libsource (lib "eagle-import") (part "RESISTOR_?_06031K"))
    )
    (comp (ref "R111")
      (value "RESISTOR_0603_DNP")
      (footprint "eagle-import:0603-RES")
      (fields (field (name "RESISTANCE") "DNP"))
      (libsource (lib "eagle-import") (part "RESISTOR_?_0603DNP"))
    )
    (comp (ref "U101")
      (value "LTC6994-2")
      (footprint "eagle-import:SOT-23-6")
      (libsource (lib "eagle-import") (part "LTC6994-2"))
    )
    (comp (ref "U103")
      (value "DCM4623TD2J13D0T70")
      (footprint "eagle-import:DCM4623")
      (fields (field (name "MANUFACTURER") "Vicor"))
      (libsource (lib "eagle-import") (part "DCM4623TD2J13D0T70"))
    )
    (comp (ref "XF1")
      (value "FUSE_HOLDER_MINIBLADEPTH")
      (footprint "eagle-import:3568")
      (fields (field (name "MANUFACTURER") "Keystone") (field (name "MPN") "3568"))
      (libsource (lib "eagle-import") (part "FUSE_HOLDER_PTHMINIBLADE"))
    )
    (comp (ref "C2")
      (value "CAPACITOR_2220_630V_0.1UF")
      (footprint "eagle-import:2220-CAP")
      (fields
        (field (name "CAPACITANCE") "0.1uF")
        (field (name "MANUFACTURER") "TDK Coporation")
        (field (name "MPN") "C5750CH2J104K280KC")
        (field (name "TOLERANCE") "10%")
        (field (name "VOLTAGE") "630V")
      )
      (libsource (lib "eagle-import") (part "CAPACITOR_?_2220630V_0.1UF"))
    )
    (comp (ref "C3")
      (value "CAPACITOR_2220_630V_1UF")
      (footprint "eagle-import:2220-CAP")
      (fields
        (field (name "CAPACITANCE") "1µF")
        (field (name "MANUFACTURER") "Knowles Syfer")
        (field (name "MPN") "2220Y6300105KXTWS2")
        (field (name "TOLERANCE") "10%")
        (field (name "VOLTAGE") "630V")
      )
      (libsource (lib "eagle-import") (part "CAPACITOR_?_2220630V_1UF"))
    )
    (comp (ref "C4")
      (value "CAPACITOR_1206_250V_0.1UF")
      (footprint "eagle-import:1206-CAP")
      (fields
        (field (name "CAPACITANCE") "0.1uF")
        (field (name "MANUFACTURER") "TDK Corporation")
        (field (name "MPN") "C3216X7R2E104K160AM")
        (field (name "TOLERANCE") "10%")
        (field (name "VOLTAGE") "250V")
      )
      (libsource (lib "eagle-import") (part "CAPACITOR_?_1206250V_0.1UF"))
    )
    (comp (ref "C5")
      (value "CAPACITOR_2220_250V_1UF")
      (footprint "eagle-import:2220-CAP")
      (fields
        (field (name "CAPACITANCE") "1µF")
        (field (name "MANUFACTURER") "TDK Corporation")
        (field (name "MPN") "C5750X7R2E105K230KA")
        (field (name "TOLERANCE") "10%")
        (field (name "VOLTAGE") "250V")
      )
      (libsource (lib "eagle-import") (part "CAPACITOR_?_2220250V_1UF"))
    )
    (comp (ref "C7")
      (value "CAPACITOR_0603_10V_10NF")
      (footprint "eagle-import:0603-CAP")
      (fields
        (field (name "CAPACITANCE") "10nF")
        (field (name "MANUFACTURER") "Yageo")
        (field (name "MPN") "CC0603KRX7R6BB103")
        (field (name "TOLERANCE") "10%")
        (field (name "VOLTAGE") "10V")
      )
      (libsource (lib "eagle-import") (part "CAPACITOR_?_060310V_10NF"))
    )
    (comp (ref "C8")
      (value "CAPACITOR_2220_250V_1UF")
      (footprint "eagle-import:2220-CAP")
      (fields
        (field (name "CAPACITANCE") "1µF")
        (field (name "MANUFACTURER") "TDK Corporation")
        (field (name "MPN") "C5750X7R2E105K230KA")
        (field (name "TOLERANCE") "10%")
        (field (name "VOLTAGE") "250V")
      )
      (libsource (lib "eagle-import") (part "CAPACITOR_?_2220250V_1UF"))
    )
    (comp (ref "C11")
      (value "CAPACITOR_1206_250V_0.1UF")
      (footprint "eagle-import:1206-CAP")
      (fields
        (field (name "CAPACITANCE") "0.1uF")
        (field (name "MANUFACTURER") "TDK Corporation")
        (field (name "MPN") "C3216X7R2E104K160AM")
        (field (name "TOLERANCE") "10%")
        (field (name "VOLTAGE") "250V")
      )
      (libsource (lib "eagle-import") (part "CAPACITOR_?_1206250V_0.1UF"))
    )
    (comp (ref "C12")
      (value "CAPACITOR_0805_25V_22UF")
      (footprint "eagle-import:0805-CAP")
      (fields
        (field (name "CAPACITANCE") "22µF")
        (field (name "MANUFACTURER") "Yageo")
        (field (name "MPN") "CC0805MKX5R8BB226")
        (field (name "TOLERANCE") "20%")
        (field (name "VOLTAGE") "25V")
      )
      (libsource (lib "eagle-import") (part "CAPACITOR_?_080525V_22UF"))
    )
    (comp (ref "C13")
      (value "CAPACITOR_0603_25V_1UF")
      (footprint "eagle-import:0603-CAP")
      (fields
        (field (name "CAPACITANCE") "1µF")
        (field (name "MANUFACTURER") "Samsung Electro-Mechanics")
        (field (name "MPN") "CL10B105KA8NNNC")
        (field (name "TOLERANCE") "10%")
        (field (name "VOLTAGE") "25V")
      )
      (libsource (lib "eagle-import") (part "CAPACITOR_?_060325V_1UF"))
    )
    (comp (ref "C14")
      (value "CAPACITOR_0603_25V_0.1UF")
      (footprint "eagle-import:0603-CAP")
      (fields
        (field (name "CAPACITANCE") "0.1µF")
        (field (name "MANUFACTURER") "Samsung Electro-Mechanics")
        (field (name "MPN") "CL10B104KA8NNNC")
        (field (name "TOLERANCE") "10%")
        (field (name "VOLTAGE") "25V")
      )
      (libsource (lib "eagle-import") (part "CAPACITOR_?_060325V_0.1UF"))
    )
    (comp (ref "C15")
      (value "CAPACITOR_0603_10V_10NF")
      (footprint "eagle-import:0603-CAP")
      (fields
        (field (name "CAPACITANCE") "10nF")
        (field (name "MANUFACTURER") "Yageo")
        (field (name "MPN") "CC0603KRX7R6BB103")
        (field (name "TOLERANCE") "10%")
        (field (name "VOLTAGE") "10V")
      )
      (libsource (lib "eagle-import") (part "CAPACITOR_?_060310V_10NF"))
    )
    (comp (ref "C16")
      (value "CAPACITOR_0603_10V_10NF")
      (footprint "eagle-import:0603-CAP")
      (fields
        (field (name "CAPACITANCE") "10nF")
        (field (name "MANUFACTURER") "Yageo")
        (field (name "MPN") "CC0603KRX7R6BB103")
        (field (name "TOLERANCE") "10%")
        (field (name "VOLTAGE") "10V")
      )
      (libsource (lib "eagle-import") (part "CAPACITOR_?_060310V_10NF"))
    )
    (comp (ref "C17")
      (value "CAPACITOR_0603_10V_1UF")
      (footprint "eagle-import:0603-CAP")
      (fields
        (field (name "CAPACITANCE") "1µF")
        (field (name "MANUFACTURER") "Yageo")
        (field (name "MPN") "CC0603KRX7R6BB105")
        (field (name "TOLERANCE") "10%")
        (field (name "VOLTAGE") "10V")
      )
      (libsource (lib "eagle-import") (part "CAPACITOR_?_060310V_1UF"))
    )
    (comp (ref "C18")
      (value "CAPACITOR_0603_10V_1UF")
      (footprint "eagle-import:0603-CAP")
      (fields
        (field (name "CAPACITANCE") "1µF")
        (field (name "MANUFACTURER") "Yageo")
        (field (name "MPN") "CC0603KRX7R6BB105")
        (field (name "TOLERANCE") "10%")
        (field (name "VOLTAGE") "10V")
      )
      (libsource (lib "eagle-import") (part "CAPACITOR_?_060310V_1UF"))
    )
    (comp (ref "C19")
      (value "CAPACITOR_0603_10V_1UF")
      (footprint "eagle-import:0603-CAP")
      (fields
        (field (name "CAPACITANCE") "1µF")
        (field (name "MANUFACTURER") "Yageo")
        (field (name "MPN") "CC0603KRX7R6BB105")
        (field (name "TOLERANCE") "10%")
        (field (name "VOLTAGE") "10V")
      )
      (libsource (lib "eagle-import") (part "CAPACITOR_?_060310V_1UF"))
    )
    (comp (ref "C20")
      (value "CAPACITOR_0603_10V_1UF")
      (footprint "eagle-import:0603-CAP")
      (fields
        (field (name "CAPACITANCE") "1µF")
        (field (name "MANUFACTURER") "Yageo")
        (field (name "MPN") "CC0603KRX7R6BB105")
        (field (name "TOLERANCE") "10%")
        (field (name "VOLTAGE") "10V")
      )
      (libsource (lib "eagle-import") (part "CAPACITOR_?_060310V_1UF"))
    )
    (comp (ref "C21")
      (value "CAPACITOR_0603_10V_1UF")
      (footprint "eagle-import:0603-CAP")
      (fields
        (field (name "CAPACITANCE") "1µF")
        (field (name "MANUFACTURER") "Yageo")
        (field (name "MPN") "CC0603KRX7R6BB105")
        (field (name "TOLERANCE") "10%")
        (field (name "VOLTAGE") "10V")
      )
      (libsource (lib "eagle-import") (part "CAPACITOR_?_060310V_1UF"))
    )
    (comp (ref "C22")
      (value "CAPACITOR_0603_10V_1UF")
      (footprint "eagle-import:0603-CAP")
      (fields
        (field (name "CAPACITANCE") "1µF")
        (field (name "MANUFACTURER") "Yageo")
        (field (name "MPN") "CC0603KRX7R6BB105")
        (field (name "TOLERANCE") "10%")
        (field (name "VOLTAGE") "10V")
      )
      (libsource (lib "eagle-import") (part "CAPACITOR_?_060310V_1UF"))
    )
    (comp (ref "C102")
      (value "CAPACITOR_0603_10V_0.1UF")
      (footprint "eagle-import:0603-CAP")
      (fields
        (field (name "CAPACITANCE") "0.1µF")
        (field (name "MANUFACTURER") "Vishay Vitramon")
        (field (name "MPN") "VJ0603Y104JXQPW1BC")
        (field (name "TOLERANCE") "5%")
        (field (name "VOLTAGE") "10V")
      )
      (libsource (lib "eagle-import") (part "CAPACITOR_?_060310V_0.1UF"))
    )
    (comp (ref "C103")
      (value "CAPACITOR_0603_10V_1UF")
      (footprint "eagle-import:0603-CAP")
      (fields
        (field (name "CAPACITANCE") "1µF")
        (field (name "MANUFACTURER") "Yageo")
        (field (name "MPN") "CC0603KRX7R6BB105")
        (field (name "TOLERANCE") "10%")
        (field (name "VOLTAGE") "10V")
      )
      (libsource (lib "eagle-import") (part "CAPACITOR_?_060310V_1UF"))
    )
    (comp (ref "C107")
      (value "CAPACITOR_0603_10V_1UF")
      (footprint "eagle-import:0603-CAP")
      (fields
        (field (name "CAPACITANCE") "1µF")
        (field (name "MANUFACTURER") "Yageo")
        (field (name "MPN") "CC0603KRX7R6BB105")
        (field (name "TOLERANCE") "10%")
        (field (name "VOLTAGE") "10V")
      )
      (libsource (lib "eagle-import") (part "CAPACITOR_?_060310V_1UF"))
    )
    (comp (ref "C108")
      (value "CAPACITOR_0603_10V_0.1UF")
      (footprint "eagle-import:0603-CAP")
      (fields
        (field (name "CAPACITANCE") "0.1µF")
        (field (name "MANUFACTURER") "Vishay Vitramon")
        (field (name "MPN") "VJ0603Y104JXQPW1BC")
        (field (name "TOLERANCE") "5%")
        (field (name "VOLTAGE") "10V")
      )
      (libsource (lib "eagle-import") (part "CAPACITOR_?_060310V_0.1UF"))
    )
    (comp (ref "C109")
      (value "CAPACITOR_2220_250V_1UF")
      (footprint "eagle-import:2220-CAP")
      (fields
        (field (name "CAPACITANCE") "1µF")
        (field (name "MANUFACTURER") "TDK Corporation")
        (field (name "MPN") "C5750X7R2E105K230KA")
        (field (name "TOLERANCE") "10%")
        (field (name "VOLTAGE") "250V")
      )
      (libsource (lib "eagle-import") (part "CAPACITOR_?_2220250V_1UF"))
    )
    (comp (ref "D3")
      (value "SCHOTTKY_SOD323_30V")
      (footprint "eagle-import:SOD-323")
      (fields
        (field (name "MANUFACTURER") "Toshiba Semiconductor and Storage")
        (field (name "MPN") "CUS08F30")
        (field (name "VOLTAGE") "30V")
      )
      (libsource (lib "eagle-import") (part "SCHOTTKY_?_SOD32330V"))
    )
    (comp (ref "D4")
      (value "LED_0603_BLUE")
      (footprint "eagle-import:0603-LED")
      (fields
        (field (name "COLOR") "Blue")
        (field (name "MANUFACTURER") "Kingbright")
        (field (name "MPN") "APT1608VBC/D")
      )
      (libsource (lib "eagle-import") (part "LED_?_0603BLUE"))
    )
    (comp (ref "D102")
      (value "RECTIFIER_400V_SOD123")
      (footprint "eagle-import:SOD123F")
      (fields
        (field (name "MANUFACTURER") "Diodes Incorporated")
        (field (name "MPN") "US1GWF-7")
        (field (name "VOLTAGE") "400V")
      )
      (libsource (lib "eagle-import") (part "RECTIFIER__?SOD123400V"))
    )
    (comp (ref "L3")
      (value "INDUCTOR_SRU1048_330UH")
      (footprint "eagle-import:SRU1048")
      (fields
        (field (name "INDUCTANCE") "330µH")
        (field (name "MANUFACTURER") "Bourns Inc.")
        (field (name "MPN") "SRU1048-331Y")
        (field (name "TOLERANCE") "30%")
      )
      (libsource (lib "eagle-import") (part "INDUCTOR_?_SRU1048330UH"))
    )
    (comp (ref "R2")
      (value "RESISTOR_0603_39")
      (footprint "eagle-import:0603-RES")
      (fields
        (field (name "MANUFACTURER") "Yageo")
        (field (name "MPN") "RT0603BRD0739RL")
        (field (name "POWER") "0.1W")
        (field (name "RESISTANCE") "39")
      )
      (libsource (lib "eagle-import") (part "RESISTOR_?_060339"))
    )
    (comp (ref "R5")
      (value "RESISTOR_0603_10K")
      (footprint "eagle-import:0603-RES")
      (fields
        (field (name "MANUFACTURER") "Yageo")
        (field (name "MPN") "RC0603FR-0710KL")
        (field (name "POWER") "0.1W")
        (field (name "RESISTANCE") "10k")
      )
      (libsource (lib "eagle-import") (part "RESISTOR_?_060310K"))
    )
    (comp (ref "R6")
      (value "RESISTOR_0603_1K")
      (footprint "eagle-import:0603-RES")
      (fields
        (field (name "MANUFACTURER") "Yageo")
        (field (name "MPN") "RC0603FR-071KL")
        (field (name "POWER") "0.1W")
        (field (name "RESISTANCE") "1k")
      )
      (libsource (lib "eagle-import") (part "RESISTOR_?_06031K"))
    )
    (comp (ref "R11")
      (value "RESISTOR_0603_HV750K")
      (footprint "eagle-import:0603-RES")
      (fields
        (field (name "MANUFACTURER") "Rohm")
        (field (name "MPN") "KTR03EZPF7502")
        (field (name "POWER") "0.1W")
        (field (name "RESISTANCE") "750k")
      )
      (libsource (lib "eagle-import") (part "RESISTOR_?_0603HV750K"))
    )
    (comp (ref "R12")
      (value "RESISTOR_0603_HV750K")
      (footprint "eagle-import:0603-RES")
      (fields
        (field (name "MANUFACTURER") "Rohm")
        (field (name "MPN") "KTR03EZPF7502")
        (field (name "POWER") "0.1W")
        (field (name "RESISTANCE") "750k")
      )
      (libsource (lib "eagle-import") (part "RESISTOR_?_0603HV750K"))
    )
    (comp (ref "R14")
      (value "RESISTOR_0603_360K")
      (footprint "eagle-import:0603-RES")
      (fields
        (field (name "MANUFACTURER") "Rohm Semiconductor")
        (field (name "MPN") "KTR03EZPF3603")
        (field (name "POWER") "0.1W")
        (field (name "RESISTANCE") "360k")
      )
      (libsource (lib "eagle-import") (part "RESISTOR_?_0603360K"))
    )
    (comp (ref "R15")
      (value "RESISTOR_0603_360K")
      (footprint "eagle-import:0603-RES")
      (fields
        (field (name "MANUFACTURER") "Rohm Semiconductor")
        (field (name "MPN") "KTR03EZPF3603")
        (field (name "POWER") "0.1W")
        (field (name "RESISTANCE") "360k")
      )
      (libsource (lib "eagle-import") (part "RESISTOR_?_0603360K"))
    )
    (comp (ref "R16")
      (value "RESISTOR_0603_HV75K")
      (footprint "eagle-import:0603-RES")
      (fields
        (field (name "MANUFACTURER") "Rohm")
        (field (name "MPN") "KTR03EZPF7503")
        (field (name "POWER") "0.1W")
        (field (name "RESISTANCE") "75k")
      )
      (libsource (lib "eagle-import") (part "RESISTOR_?_0603HV75K"))
    )
    (comp (ref "R17")
      (value "RESISTOR_0603_HV75K")
      (footprint "eagle-import:0603-RES")
      (fields
        (field (name "MANUFACTURER") "Rohm")
        (field (name "MPN") "KTR03EZPF7503")
        (field (name "POWER") "0.1W")
        (field (name "RESISTANCE") "75k")
      )
      (libsource (lib "eagle-import") (part "RESISTOR_?_0603HV75K"))
    )
    (comp (ref "R18")
      (value "RESISTOR_0603_HV75K")
      (footprint "eagle-import:0603-RES")
      (fields
        (field (name "MANUFACTURER") "Rohm")
        (field (name "MPN") "KTR03EZPF7503")
        (field (name "POWER") "0.1W")
        (field (name "RESISTANCE") "75k")
      )
      (libsource (lib "eagle-import") (part "RESISTOR_?_0603HV75K"))
    )
    (comp (ref "R19")
      (value "RESISTOR_0603_HV75K")
      (footprint "eagle-import:0603-RES")
      (fields
        (field (name "MANUFACTURER") "Rohm")
        (field (name "MPN") "KTR03EZPF7503")
        (field (name "POWER") "0.1W")
        (field (name "RESISTANCE") "75k")
      )
      (libsource (lib "eagle-import") (part "RESISTOR_?_0603HV75K"))
    )
    (comp (ref "R20")
      (value "RESISTOR_0603_33.2K")
      (footprint "eagle-import:0603-RES")
      (fields
        (field (name "MANUFACTURER") "Panasonic Electronic Components")
        (field (name "MPN") "ERJ-PB3B3322V")
        (field (name "POWER") "0.1W")
        (field (name "RESISTANCE") "33.2k")
      )
      (libsource (lib "eagle-import") (part "RESISTOR_?_060333.2K"))
    )
    (comp (ref "R21")
      (value "RESISTOR_0603_33.2K")
      (footprint "eagle-import:0603-RES")
      (fields
        (field (name "MANUFACTURER") "Panasonic Electronic Components")
        (field (name "MPN") "ERJ-PB3B3322V")
        (field (name "POWER") "0.1W")
        (field (name "RESISTANCE") "33.2k")
      )
      (libsource (lib "eagle-import") (part "RESISTOR_?_060333.2K"))
    )
    (comp (ref "R107")
      (value "RESISTOR_0603_75K")
      (footprint "eagle-import:0603-RES")
      (fields
        (field (name "MANUFACTURER") "Yageo")
        (field (name "MPN") "RT0603BRE0775KL")
        (field (name "POWER") "0.1W")
        (field (name "RESISTANCE") "75k")
      )
      (libsource (lib "eagle-import") (part "RESISTOR_?_060375K"))
    )
    (comp (ref "R108")
      (value "RESISTOR_0603_8.35K")
      (footprint "eagle-import:0603-RES")
      (fields
        (field (name "MANUFACTURER") "Vishay Dale Thin Film")
        (field (name "MPN") "PTN0603E8351BST1")
        (field (name "POWER") "0.15W")
        (field (name "RESISTANCE") "8.35k")
      )
      (libsource (lib "eagle-import") (part "RESISTOR_?_06038.35K"))
    )
    (comp (ref "R109")
      (value "RESISTOR_0603_13.3K")
      (footprint "eagle-import:0603-RES")
      (fields
        (field (name "MANUFACTURER") "Panasonic Electronic Components")
        (field (name "MPN") "ERJ-PB3B1332V")
        (field (name "POWER") "0.2W")
        (field (name "RESISTANCE") "13.3k")
      )
      (libsource (lib "eagle-import") (part "RESISTOR_?_060313.3K"))
    )
    (comp (ref "R110")
      (value "RESISTOR_0805_976K")
      (footprint "eagle-import:0805-RES")
      (fields
        (field (name "MANUFACTURER") "Panasonic Electronic Components")
        (field (name "MPN") "  ERJ-PB6B9763V")
        (field (name "POWER") "0.25W")
        (field (name "RESISTANCE") "976k")
      )
      (libsource (lib "eagle-import") (part "RESISTOR_?_0805976K"))
    )
    (comp (ref "R112")
      (value "RESISTOR_0805_HV365K")
      (footprint "eagle-import:0805-RES")
      (fields
        (field (name "MANUFACTURER") "Rohm")
        (field (name "MPN") "KTR10EZPF3653")
        (field (name "POWER") "0.125W")
        (field (name "RESISTANCE") "365k")
      )
      (libsource (lib "eagle-import") (part "RESISTOR_?_0805HV365K"))
    )
    (comp (ref "R113")
      (value "RESISTOR_0603_3.32K")
      (footprint "eagle-import:0603-RES")
      (fields
        (field (name "MANUFACTURER") "Yageo")
        (field (name "MPN") "RT0603BRD073K32L")
        (field (name "POWER") "0.1W")
        (field (name "RESISTANCE") "3.32k")
      )
      (libsource (lib "eagle-import") (part "RESISTOR_?_06033.32K"))
    )
    (comp (ref "TP9")
      (value "TEST_POINT")
      (footprint "eagle-import:MICRO_MINIATURE")
      (fields (field (name "MPN") "5015") (field (name "MANUFACTURER") "Keystone Electronics"))
      (libsource (lib "eagle-import") (part "TEST_POINT"))
    )
    (comp (ref "TP12")
      (value "TEST_POINT")
      (footprint "eagle-import:MICRO_MINIATURE")
      (fields (field (name "MPN") "5015") (field (name "MANUFACTURER") "Keystone Electronics"))
      (libsource (lib "eagle-import") (part "TEST_POINT"))
    )
    (comp (ref "TP13")
      (value "TEST_POINT")
      (footprint "eagle-import:MICRO_MINIATURE")
      (fields (field (name "MPN") "5015") (field (name "MANUFACTURER") "Keystone Electronics"))
      (libsource (lib "eagle-import") (part "TEST_POINT"))
    )
    (comp (ref "U1")
      (value "LTC3639")
      (footprint "eagle-import:MSE16(12)")
      (fields (field (name "MPN") "LTC3639EMSE#TRPBF ") (field (name "MANUFACTURER") "Analog Devices Inc."))
      (libsource (lib "eagle-import") (part "LTC3639"))
    )
    (comp (ref "U2")
      (value "ISO224B_AIRGAP")
      (footprint "eagle-import:SOIC-08(WIDE,0.295_)-AIRGAP")
      (fields (field (name "MANUFACTURER") "Texas Instruments") (field (name "MPN") "ISO224BDWVR"))
      (libsource (lib "eagle-import") (part "ISO224_AIRGAPB"))
    )
    (comp (ref "U3")
      (value "ISO224B_AIRGAP")
      (footprint "eagle-import:SOIC-08(WIDE,0.295_)-AIRGAP")
      (fields (field (name "MANUFACTURER") "Texas Instruments") (field (name "MPN") "ISO224BDWVR"))
      (libsource (lib "eagle-import") (part "ISO224_AIRGAPB"))
    )
    (comp (ref "U102")
      (value "VOLTAGE_REGULATOR_ADJ_LR8_DPAK")
      (footprint "eagle-import:DPAK(2-7K1S)")
      (fields (field (name "MANUFACTURER") "Microchip Technology") (field (name "MPN") "LR8K4-G"))
      (libsource (lib "eagle-import") (part "VOLTAGE_REGULATOR_ADJ__?DPAKLR8"))
    )
  )
  (nets
    (net (code "1") (name "+5V") (class "Default")
      (node (ref "C101") (pin "1") (pinfunction "1_1") (pintype "passive"))
      (node (ref "C102") (pin "1") (pinfunction "1_1") (pintype "passive"))
      (node (ref "C103") (pin "1") (pinfunction "1_1") (pintype "passive"))
      (node (ref "C105") (pin "1") (pinfunction "1_1") (pintype "passive"))
      (node (ref "C106") (pin "1") (pinfunction "1_1") (pintype "passive"))
      (node (ref "C107") (pin "1") (pinfunction "1_1") (pintype "passive"))
      (node (ref "C108") (pin "1") (pinfunction "1_1") (pintype "passive"))
      (node (ref "C23") (pin "1") (pinfunction "1_1") (pintype "passive"))
      (node (ref "R102") (pin "2") (pinfunction "2_2") (pintype "passive"))
      (node (ref "R105") (pin "2") (pinfunction "2_2") (pintype "passive"))
      (node (ref "R26") (pin "1") (pinfunction "1_1") (pintype "passive"))
      (node (ref "TP20") (pin "1") (pinfunction "P$1_1") (pintype "passive"))
      (node (ref "U100") (pin "5") (pinfunction "V+_5") (pintype "power_in"))
      (node (ref "U101") (pin "5") (pinfunction "V+_5") (pintype "power_in"))
      (node (ref "U2") (pin "8") (pinfunction "VDD2_8") (pintype "power_in"))
      (node (ref "U3") (pin "8") (pinfunction "VDD2_8") (pintype "power_in"))
      (node (ref "U4") (pin "2") (pinfunction "OUT_2") (pintype "power_in"))
      (node (ref "U4") (pin "4") (pinfunction "OUT_4") (pintype "power_in"))
    )
    (net (code "2") (name "+12V") (class "Default")
      (node (ref "C100") (pin "1") (pinfunction "1_1") (pintype "passive"))
      (node (ref "C104") (pin "1") (pinfunction "1_1") (pintype "passive"))
      (node (ref "J4") (pin "1") (pinfunction "1_1") (pintype "passive"))
      (node (ref "R25") (pin "2") (pinfunction "2_2") (pintype "passive"))
      (node (ref "TP19") (pin "1") (pinfunction "P$1_1") (pintype "passive"))
      (node (ref "U4") (pin "3") (pinfunction "IN_3") (pintype "power_in"))
    )
    (net (code "3") (name "DCDC+") (class "Default")
      (node (ref "J1") (pin "1") (pinfunction "1_1") (pintype "passive"))
      (node (ref "J1") (pin "3") (pinfunction "3_3") (pintype "passive"))
      (node (ref "R1") (pin "2") (pinfunction "2_2") (pintype "passive"))
      (node (ref "TP1") (pin "1") (pinfunction "P$1_1") (pintype "passive"))
      (node (ref "XF1") (pin "3") (pinfunction "2_3") (pintype "passive"))
      (node (ref "XF1") (pin "4") (pinfunction "2_4") (pintype "passive"))
    )
    (net (code "4") (name "DCDC-") (class "Default")
      (node (ref "C1") (pin "-") (pinfunction "MINUS_-") (pintype "passive"))
      (node (ref "C110") (pin "1") (pinfunction "1_1") (pintype "passive"))
      (node (ref "C111") (pin "1") (pinfunction "1_1") (pintype "passive"))
      (node (ref "C112") (pin "1") (pinfunction "1_1") (pintype "passive"))
      (node (ref "D1") (pin "1") (pinfunction "C_1") (pintype "passive"))
      (node (ref "J1") (pin "2") (pinfunction "2_2") (pintype "passive"))
      (node (ref "J1") (pin "4") (pinfunction "4_4") (pintype "passive"))
      (node (ref "TP2") (pin "1") (pinfunction "P$1_1") (pintype "passive"))
      (node (ref "U103") (pin "7") (pinfunction "-OUT_7") (pintype "power_in"))
      (node (ref "U103") (pin "9") (pinfunction "-OUT_9") (pintype "power_in"))
    )
    (net (code "5") (name "DCDC_ENABLE") (class "Default")
      (node (ref "D5") (pin "3") (pinfunction "C_3") (pintype "passive"))
      (node (ref "R23") (pin "2") (pinfunction "2_2") (pintype "passive"))
      (node (ref "R24") (pin "1") (pinfunction "1_1") (pintype "passive"))
      (node (ref "R28") (pin "2") (pinfunction "2_2") (pintype "passive"))
      (node (ref "U100") (pin "4") (pinfunction "OUT_4") (pintype "bidirectional"))
      (node (ref "U101") (pin "1") (pinfunction "IN_1") (pintype "bidirectional"))
    )
    (net (code "6") (name "ENABLE") (class "Default")
      (node (ref "K100") (pin "4") (pinfunction "CONTACT2_4") (pintype "bidirectional"))
      (node (ref "U103") (pin "3") (pinfunction "EN_3") (pintype "input"))
    )
    (net (code "7") (name "GND") (class "Default")
      (node (ref "C100") (pin "2") (pinfunction "2_2") (pintype "passive"))
      (node (ref "C101") (pin "2") (pinfunction "2_2") (pintype "passive"))
      (node (ref "C102") (pin "2") (pinfunction "2_2") (pintype "passive"))
      (node (ref "C103") (pin "2") (pinfunction "2_2") (pintype "passive"))
      (node (ref "C104") (pin "2") (pinfunction "2_2") (pintype "passive"))
      (node (ref "C105") (pin "2") (pinfunction "2_2") (pintype "passive"))
      (node (ref "C106") (pin "2") (pinfunction "2_2") (pintype "passive"))
      (node (ref "C107") (pin "2") (pinfunction "2_2") (pintype "passive"))
      (node (ref "C108") (pin "2") (pinfunction "2_2") (pintype "passive"))
      (node (ref "C23") (pin "2") (pinfunction "2_2") (pintype "passive"))
      (node (ref "D10") (pin "1") (pinfunction "C_1") (pintype "passive"))
      (node (ref "D100") (pin "A") (pinfunction "A_A") (pintype "passive"))
      (node (ref "D11") (pin "1") (pinfunction "C_1") (pintype "passive"))
      (node (ref "D5") (pin "1") (pinfunction "A_1") (pintype "passive"))
      (node (ref "D6") (pin "1") (pinfunction "C_1") (pintype "passive"))
      (node (ref "D7") (pin "1") (pinfunction "C_1") (pintype "passive"))
      (node (ref "D8") (pin "1") (pinfunction "C_1") (pintype "passive"))
      (node (ref "D9") (pin "1") (pinfunction "C_1") (pintype "passive"))
      (node (ref "J4") (pin "4") (pinfunction "4_4") (pintype "passive"))
      (node (ref "K100") (pin "2") (pinfunction "CONTROL-_2") (pintype "passive"))
      (node (ref "K2") (pin "3") (pinfunction "COIL-_3") (pintype "bidirectional"))
      (node (ref "K3") (pin "2") (pinfunction "CONTROL-_2") (pintype "passive"))
      (node (ref "Q1") (pin "2") (pinfunction "S_2") (pintype "passive"))
      (node (ref "R100") (pin "1") (pinfunction "1_1") (pintype "passive"))
      (node (ref "R101") (pin "1") (pinfunction "1_1") (pintype "passive"))
      (node (ref "R103") (pin "1") (pinfunction "1_1") (pintype "passive"))
      (node (ref "R104") (pin "1") (pinfunction "1_1") (pintype "passive"))
      (node (ref "R23") (pin "1") (pinfunction "1_1") (pintype "passive"))
      (node (ref "TP22") (pin "1") (pinfunction "P$1_1") (pintype "passive"))
      (node (ref "U100") (pin "2") (pinfunction "GND_2") (pintype "power_in"))
      (node (ref "U101") (pin "2") (pinfunction "GND_2") (pintype "power_in"))
      (node (ref "U2") (pin "5") (pinfunction "GND2_5") (pintype "power_in"))
      (node (ref "U3") (pin "5") (pinfunction "GND2_5") (pintype "power_in"))
      (node (ref "U4") (pin "1") (pinfunction "GND_1") (pintype "power_in"))
    )
    (net (code "8") (name "IP+") (class "Default")
      (node (ref "J4") (pin "5") (pinfunction "5_5") (pintype "passive"))
      (node (ref "TP15") (pin "1") (pinfunction "P$1_1") (pintype "passive"))
      (node (ref "U3") (pin "7") (pinfunction "OUTP_7") (pintype "output"))
    )
    (net (code "9") (name "IP-") (class "Default")
      (node (ref "J4") (pin "6") (pinfunction "6_6") (pintype "passive"))
      (node (ref "TP14") (pin "1") (pinfunction "P$1_1") (pintype "passive"))
      (node (ref "U3") (pin "6") (pinfunction "OUTN_6") (pintype "output"))
    )
    (net (code "10") (name "IT+") (class "Default")
      (node (ref "J4") (pin "7") (pinfunction "7_7") (pintype "passive"))
      (node (ref "TP16") (pin "1") (pinfunction "P$1_1") (pintype "passive"))
      (node (ref "U2") (pin "7") (pinfunction "OUTP_7") (pintype "output"))
    )
    (net (code "11") (name "IT-") (class "Default")
      (node (ref "J4") (pin "8") (pinfunction "8_8") (pintype "passive"))
      (node (ref "TP17") (pin "1") (pinfunction "P$1_1") (pintype "passive"))
      (node (ref "U2") (pin "6") (pinfunction "OUTN_6") (pintype "output"))
    )
    (net (code "12") (name "LED+") (class "Default")
      (node (ref "J2") (pin "3") (pinfunction "3_3") (pintype "passive"))
      (node (ref "R9") (pin "2") (pinfunction "2_2") (pintype "passive"))
    )
    (net (code "13") (name "LR8_O") (class "Default")
      (node (ref "C4") (pin "1") (pinfunction "1_1") (pintype "passive"))
      (node (ref "C5") (pin "1") (pinfunction "1_1") (pintype "passive"))
      (node (ref "D102") (pin "A") (pinfunction "A_A") (pintype "passive"))
      (node (ref "D3") (pin "A") (pinfunction "A_A") (pintype "passive"))
      (node (ref "R113") (pin "2") (pinfunction "2_2") (pintype "passive"))
      (node (ref "R5") (pin "1") (pinfunction "1_1") (pintype "passive"))
      (node (ref "TP9") (pin "1") (pinfunction "P$1_1") (pintype "passive"))
      (node (ref "U102") (pin "2") (pinfunction "OUT_2") (pintype "power_in"))
    )
    (net (code "14") (name "Net-(C1-PLUS)") (class "Default")
      (node (ref "C1") (pin "+") (pinfunction "PLUS_+") (pintype "passive"))
      (node (ref "C110") (pin "2") (pinfunction "2_2") (pintype "passive"))
      (node (ref "C111") (pin "2") (pinfunction "2_2") (pintype "passive"))
      (node (ref "C112") (pin "2") (pinfunction "2_2") (pintype "passive"))
      (node (ref "U103") (pin "6") (pinfunction "+OUT_6") (pintype "power_in"))
      (node (ref "U103") (pin "8") (pinfunction "+OUT_8") (pintype "power_in"))
      (node (ref "XF1") (pin "1") (pinfunction "1_1") (pintype "passive"))
      (node (ref "XF1") (pin "2") (pinfunction "1_2") (pintype "passive"))
    )
    (net (code "15") (name "Net-(C7-Pad2)") (class "Default")
      (node (ref "C7") (pin "2") (pinfunction "2_2") (pintype "passive"))
      (node (ref "R5") (pin "2") (pinfunction "2_2") (pintype "passive"))
    )
    (net (code "16") (name "Net-(D1-A)") (class "Default")
      (node (ref "D1") (pin "2") (pinfunction "A_2") (pintype "passive"))
      (node (ref "R1") (pin "1") (pinfunction "1_1") (pintype "passive"))
    )
    (net (code "17") (name "Net-(D2-A)") (class "Default")
      (node (ref "D2") (pin "2") (pinfunction "A_2") (pintype "passive"))
      (node (ref "R4") (pin "2") (pinfunction "2_2") (pintype "passive"))
    )
    (net (code "18") (name "Net-(D4-A)") (class "Default")
      (node (ref "D4") (pin "2") (pinfunction "A_2") (pintype "passive"))
      (node (ref "R6") (pin "1") (pinfunction "1_1") (pintype "passive"))
    )
    (net (code "19") (name "Net-(D6-A)") (class "Default")
      (node (ref "D6") (pin "2") (pinfunction "A_2") (pintype "passive"))
      (node (ref "R25") (pin "1") (pinfunction "1_1") (pintype "passive"))
    )
    (net (code "20") (name "Net-(D7-A)") (class "Default")
      (node (ref "D7") (pin "2") (pinfunction "A_2") (pintype "passive"))
      (node (ref "R27") (pin "1") (pinfunction "1_1") (pintype "passive"))
    )
    (net (code "21") (name "Net-(D8-A)") (class "Default")
      (node (ref "D8") (pin "2") (pinfunction "A_2") (pintype "passive"))
      (node (ref "R28") (pin "1") (pinfunction "1_1") (pintype "passive"))
    )
    (net (code "22") (name "Net-(D9-A)") (class "Default")
      (node (ref "D9") (pin "2") (pinfunction "A_2") (pintype "passive"))
      (node (ref "R26") (pin "2") (pinfunction "2_2") (pintype "passive"))
    )
    (net (code "23") (name "Net-(D10-A)") (class "Default")
      (node (ref "D10") (pin "2") (pinfunction "A_2") (pintype "passive"))
      (node (ref "R29") (pin "1") (pinfunction "1_1") (pintype "passive"))
    )
    (net (code "24") (name "Net-(D11-A)") (class "Default")
      (node (ref "D11") (pin "2") (pinfunction "A_2") (pintype "passive"))
      (node (ref "R30") (pin "1") (pinfunction "1_1") (pintype "passive"))
    )
    (net (code "25") (name "Net-(K1-COIL-)") (class "Default")
      (node (ref "D101") (pin "A") (pinfunction "A_A") (pintype "passive"))
      (node (ref "K1") (pin "3") (pinfunction "COIL-_3") (pintype "bidirectional"))
      (node (ref "Q1") (pin "3") (pinfunction "D_3") (pintype "passive"))
    )
    (net (code "26") (name "Net-(K1-CONTACT2)") (class "Default")
      (node (ref "K1") (pin "4") (pinfunction "CONTACT2_4") (pintype "bidirectional"))
      (node (ref "R10") (pin "1") (pinfunction "1_1") (pintype "passive"))
    )
    (net (code "27") (name "Net-(K2-CONTACT2)") (class "Default")
      (node (ref "K2") (pin "4") (pinfunction "CONTACT2_4") (pintype "bidirectional"))
      (node (ref "R13") (pin "2") (pinfunction "2_2") (pintype "passive"))
    )
    (net (code "28") (name "Net-(K3-CONTACT1)") (class "Default")
      (node (ref "K3") (pin "3") (pinfunction "CONTACT1_3") (pintype "bidirectional"))
      (node (ref "R22") (pin "2") (pinfunction "2_2") (pintype "passive"))
    )
    (net (code "29") (name "Net-(K3-CONTROL+)") (class "Default")
      (node (ref "K3") (pin "1") (pinfunction "CONTROL+_1") (pintype "passive"))
      (node (ref "R31") (pin "1") (pinfunction "1_1") (pintype "passive"))
    )
    (net (code "30") (name "Net-(K100-CONTROL+)") (class "Default")
      (node (ref "K100") (pin "1") (pinfunction "CONTROL+_1") (pintype "passive"))
      (node (ref "R106") (pin "2") (pinfunction "2_2") (pintype "passive"))
    )
    (net (code "31") (name "Net-(L1-Pad2)") (class "Default")
      (node (ref "L1") (pin "2") (pinfunction "2_2") (pintype "passive"))
      (node (ref "R3") (pin "1") (pinfunction "1_1") (pintype "passive"))
    )
    (net (code "32") (name "Net-(Q1-G)") (class "Default")
      (node (ref "Q1") (pin "1") (pinfunction "G_1") (pintype "passive"))
      (node (ref "R24") (pin "2") (pinfunction "2_2") (pintype "passive"))
    )
    (net (code "33") (name "Net-(R11-Pad1)") (class "Default")
      (node (ref "R11") (pin "1") (pinfunction "1_1") (pintype "passive"))
      (node (ref "R14") (pin "2") (pinfunction "2_2") (pintype "passive"))
    )
    (net (code "34") (name "Net-(R12-Pad1)") (class "Default")
      (node (ref "R12") (pin "1") (pinfunction "1_1") (pintype "passive"))
      (node (ref "R15") (pin "2") (pinfunction "2_2") (pintype "passive"))
    )
    (net (code "35") (name "Net-(U1-ISET)") (class "Default")
      (node (ref "R107") (pin "2") (pinfunction "2_2") (pintype "passive"))
      (node (ref "U1") (pin "11") (pinfunction "ISET_11") (pintype "bidirectional"))
    )
    (net (code "36") (name "Net-(U1-OVLO)") (class "Default")
      (node (ref "R108") (pin "2") (pinfunction "2_2") (pintype "passive"))
      (node (ref "R109") (pin "1") (pinfunction "1_1") (pintype "passive"))
      (node (ref "U1") (pin "12") (pinfunction "OVLO_12") (pintype "input"))
    )
    (net (code "37") (name "Net-(U1-RUN)") (class "Default")
      (node (ref "R109") (pin "2") (pinfunction "2_2") (pintype "passive"))
      (node (ref "R110") (pin "1") (pinfunction "1_1") (pintype "passive"))
      (node (ref "U1") (pin "14") (pinfunction "RUN_14") (pintype "input"))
    )
    (net (code "38") (name "Net-(U1-SS)") (class "Default")
      (node (ref "U1") (pin "10") (pinfunction "SS_10") (pintype "input"))
      (node (ref "U1") (pin "7") (pinfunction "VPRG1_7") (pintype "input"))
    )
    (net (code "39") (name "Net-(U1-SW)") (class "Default")
      (node (ref "L3") (pin "1") (pinfunction "1_1") (pintype "passive"))
      (node (ref "U1") (pin "1") (pinfunction "SW_1") (pintype "power_in"))
    )
    (net (code "40") (name "Net-(U1-VDD)") (class "Default")
      (node (ref "C109") (pin "1") (pinfunction "1_1") (pintype "passive"))
      (node (ref "C11") (pin "1") (pinfunction "1_1") (pintype "passive"))
      (node (ref "C7") (pin "1") (pinfunction "1_1") (pintype "passive"))
      (node (ref "C8") (pin "1") (pinfunction "1_1") (pintype "passive"))
      (node (ref "D3") (pin "C") (pinfunction "C_C") (pintype "passive"))
      (node (ref "R110") (pin "2") (pinfunction "2_2") (pintype "passive"))
      (node (ref "U1") (pin "3") (pinfunction "VDD_3") (pintype "power_in"))
    )
    (net (code "41") (name "Net-(U2-IN)") (class "Default")
      (node (ref "C16") (pin "1") (pinfunction "1_1") (pintype "passive"))
      (node (ref "R21") (pin "2") (pinfunction "2_2") (pintype "passive"))
      (node (ref "U2") (pin "2") (pinfunction "IN_2") (pintype "input"))
    )
    (net (code "42") (name "Net-(U2-VCAP)") (class "Default")
      (node (ref "C20") (pin "1") (pinfunction "1_1") (pintype "passive"))
      (node (ref "U2") (pin "1") (pinfunction "VCAP_1") (pintype "passive"))
    )
    (net (code "43") (name "Net-(U3-IN)") (class "Default")
      (node (ref "C15") (pin "1") (pinfunction "1_1") (pintype "passive"))
      (node (ref "R20") (pin "2") (pinfunction "2_2") (pintype "passive"))
      (node (ref "U3") (pin "2") (pinfunction "IN_2") (pintype "input"))
    )
    (net (code "44") (name "Net-(U3-VCAP)") (class "Default")
      (node (ref "C19") (pin "1") (pinfunction "1_1") (pintype "passive"))
      (node (ref "U3") (pin "1") (pinfunction "VCAP_1") (pintype "passive"))
    )
    (net (code "45") (name "Net-(U100-DIV)") (class "Default")
      (node (ref "R100") (pin "2") (pinfunction "2_2") (pintype "passive"))
      (node (ref "R102") (pin "1") (pinfunction "1_1") (pintype "passive"))
      (node (ref "U100") (pin "6") (pinfunction "DIV_6") (pintype "bidirectional"))
    )
    (net (code "46") (name "Net-(U100-SET)") (class "Default")
      (node (ref "R104") (pin "2") (pinfunction "2_2") (pintype "passive"))
      (node (ref "U100") (pin "3") (pinfunction "SET_3") (pintype "bidirectional"))
    )
    (net (code "47") (name "Net-(U101-DIV)") (class "Default")
      (node (ref "R103") (pin "2") (pinfunction "2_2") (pintype "passive"))
      (node (ref "R105") (pin "1") (pinfunction "1_1") (pintype "passive"))
      (node (ref "U101") (pin "6") (pinfunction "DIV_6") (pintype "bidirectional"))
    )
    (net (code "48") (name "Net-(U101-OUT)") (class "Default")
      (node (ref "R106") (pin "1") (pinfunction "1_1") (pintype "passive"))
      (node (ref "R27") (pin "2") (pinfunction "2_2") (pintype "passive"))
      (node (ref "U101") (pin "4") (pinfunction "OUT_4") (pintype "bidirectional"))
    )
    (net (code "49") (name "Net-(U101-SET)") (class "Default")
      (node (ref "R101") (pin "2") (pinfunction "2_2") (pintype "passive"))
      (node (ref "U101") (pin "3") (pinfunction "SET_3") (pintype "bidirectional"))
    )
    (net (code "50") (name "Net-(U102-ADJ)") (class "Default")
      (node (ref "R112") (pin "2") (pinfunction "2_2") (pintype "passive"))
      (node (ref "R113") (pin "1") (pinfunction "1_1") (pintype "passive"))
      (node (ref "U102") (pin "3") (pinfunction "ADJ_3") (pintype "input"))
    )
    (net (code "51") (name "Net-(U102-IN)") (class "Default")
      (node (ref "C2") (pin "1") (pinfunction "1_1") (pintype "passive"))
      (node (ref "C3") (pin "1") (pinfunction "1_1") (pintype "passive"))
      (node (ref "D102") (pin "C") (pinfunction "C_C") (pintype "passive"))
      (node (ref "R2") (pin "2") (pinfunction "2_2") (pintype "passive"))
      (node (ref "U102") (pin "1") (pinfunction "IN_1") (pintype "power_in"))
    )
    (net (code "52") (name "Net-(U103-+IN)") (class "Default")
      (node (ref "C10") (pin "1") (pinfunction "1_1") (pintype "passive"))
      (node (ref "C6") (pin "1") (pinfunction "1_1") (pintype "passive"))
      (node (ref "C9") (pin "1") (pinfunction "1_1") (pintype "passive"))
      (node (ref "L1") (pin "1") (pinfunction "1_1") (pintype "passive"))
      (node (ref "L2") (pin "1") (pinfunction "1_1") (pintype "passive"))
      (node (ref "U103") (pin "1") (pinfunction "+IN_1") (pintype "power_in"))
    )
    (net (code "53") (name "Net-(U103-FLT)") (class "Default")
      (node (ref "R4") (pin "1") (pinfunction "1_1") (pintype "passive"))
      (node (ref "U103") (pin "4") (pinfunction "FLT_4") (pintype "output"))
    )
    (net (code "54") (name "Net-(U103-TR)") (class "Default")
      (node (ref "R111") (pin "1") (pinfunction "1_1") (pintype "passive"))
      (node (ref "U103") (pin "2") (pinfunction "TR_2") (pintype "output"))
    )
    (net (code "55") (name "PACK+") (class "Default")
      (node (ref "J3") (pin "5") (pinfunction "5_5") (pintype "passive"))
      (node (ref "K1") (pin "1") (pinfunction "CONTACT1_1") (pintype "bidirectional"))
      (node (ref "K3") (pin "4") (pinfunction "CONTACT2_4") (pintype "bidirectional"))
      (node (ref "TP6") (pin "1") (pinfunction "P$1_1") (pintype "passive"))
    )
    (net (code "56") (name "PACK+FUSED") (class "Default")
      (node (ref "R11") (pin "2") (pinfunction "2_2") (pintype "passive"))
      (node (ref "R22") (pin "1") (pinfunction "1_1") (pintype "passive"))
      (node (ref "TP8") (pin "1") (pinfunction "P$1_1") (pintype "passive"))
    )
    (net (code "57") (name "PRECHARGE_OK") (class "Default")
      (node (ref "J4") (pin "3") (pinfunction "3_3") (pintype "passive"))
      (node (ref "R29") (pin "2") (pinfunction "2_2") (pintype "passive"))
      (node (ref "TP18") (pin "1") (pinfunction "P$1_1") (pintype "passive"))
      (node (ref "U100") (pin "1") (pinfunction "IN_1") (pintype "bidirectional"))
    )
    (net (code "58") (name "P_DO") (class "Default")
      (node (ref "R14") (pin "1") (pinfunction "1_1") (pintype "passive"))
      (node (ref "R16") (pin "2") (pinfunction "2_2") (pintype "passive"))
      (node (ref "R18") (pin "2") (pinfunction "2_2") (pintype "passive"))
      (node (ref "R20") (pin "1") (pinfunction "1_1") (pintype "passive"))
      (node (ref "TP13") (pin "1") (pinfunction "P$1_1") (pintype "passive"))
    )
    (net (code "59") (name "SHDN") (class "Default")
      (node (ref "D100") (pin "C") (pinfunction "C_C") (pintype "passive"))
      (node (ref "D101") (pin "C") (pinfunction "C_C") (pintype "passive"))
      (node (ref "J4") (pin "2") (pinfunction "2_2") (pintype "passive"))
      (node (ref "K1") (pin "2") (pinfunction "COIL+_2") (pintype "bidirectional"))
      (node (ref "K2") (pin "2") (pinfunction "COIL+_2") (pintype "bidirectional"))
      (node (ref "R30") (pin "2") (pinfunction "2_2") (pintype "passive"))
      (node (ref "R31") (pin "2") (pinfunction "2_2") (pintype "passive"))
      (node (ref "TP21") (pin "1") (pinfunction "P$1_1") (pintype "passive"))
    )
    (net (code "60") (name "TS+5V") (class "Default")
      (node (ref "C12") (pin "1") (pinfunction "1_1") (pintype "passive"))
      (node (ref "C13") (pin "1") (pinfunction "1_1") (pintype "passive"))
      (node (ref "C14") (pin "1") (pinfunction "1_1") (pintype "passive"))
      (node (ref "C17") (pin "1") (pinfunction "1_1") (pintype "passive"))
      (node (ref "C18") (pin "1") (pinfunction "1_1") (pintype "passive"))
      (node (ref "C21") (pin "1") (pinfunction "1_1") (pintype "passive"))
      (node (ref "C22") (pin "1") (pinfunction "1_1") (pintype "passive"))
      (node (ref "L3") (pin "2") (pinfunction "2_2") (pintype "passive"))
      (node (ref "R6") (pin "2") (pinfunction "2_2") (pintype "passive"))
      (node (ref "R9") (pin "1") (pinfunction "1_1") (pintype "passive"))
      (node (ref "TP3") (pin "1") (pinfunction "P$1_1") (pintype "passive"))
      (node (ref "U1") (pin "9") (pinfunction "VFB_9") (pintype "input"))
      (node (ref "U2") (pin "3") (pinfunction "VDD1_3") (pintype "power_in"))
      (node (ref "U3") (pin "3") (pinfunction "VDD1_3") (pintype "power_in"))
    )
    (net (code "61") (name "TS+FUSED") (class "Default")
      (node (ref "F1") (pin "2") (pinfunction "2_2") (pintype "passive"))
      (node (ref "J3") (pin "4") (pinfunction "4_4") (pintype "passive"))
      (node (ref "L2") (pin "2") (pinfunction "2_2") (pintype "passive"))
      (node (ref "R12") (pin "2") (pinfunction "2_2") (pintype "passive"))
      (node (ref "R2") (pin "1") (pinfunction "1_1") (pintype "passive"))
      (node (ref "R3") (pin "2") (pinfunction "2_2") (pintype "passive"))
    )
    (net (code "62") (name "TS+UNFUSED") (class "Default")
      (node (ref "F1") (pin "1") (pinfunction "1_1") (pintype "passive"))
      (node (ref "J3") (pin "1") (pinfunction "1_1") (pintype "passive"))
      (node (ref "J3") (pin "2") (pinfunction "2_2") (pintype "passive"))
      (node (ref "K2") (pin "1") (pinfunction "CONTACT1_1") (pintype "bidirectional"))
      (node (ref "R10") (pin "2") (pinfunction "2_2") (pintype "passive"))
      (node (ref "R7") (pin "1") (pinfunction "1_1") (pintype "passive"))
      (node (ref "TP10") (pin "1") (pinfunction "P$1_1") (pintype "passive"))
    )
    (net (code "63") (name "TS-FUSED") (class "Default")
      (node (ref "C10") (pin "2") (pinfunction "2_2") (pintype "passive"))
      (node (ref "C109") (pin "2") (pinfunction "2_2") (pintype "passive"))
      (node (ref "C11") (pin "2") (pinfunction "2_2") (pintype "passive"))
      (node (ref "C12") (pin "2") (pinfunction "2_2") (pintype "passive"))
      (node (ref "C13") (pin "2") (pinfunction "2_2") (pintype "passive"))
      (node (ref "C14") (pin "2") (pinfunction "2_2") (pintype "passive"))
      (node (ref "C15") (pin "2") (pinfunction "2_2") (pintype "passive"))
      (node (ref "C16") (pin "2") (pinfunction "2_2") (pintype "passive"))
      (node (ref "C17") (pin "2") (pinfunction "2_2") (pintype "passive"))
      (node (ref "C18") (pin "2") (pinfunction "2_2") (pintype "passive"))
      (node (ref "C19") (pin "2") (pinfunction "2_2") (pintype "passive"))
      (node (ref "C2") (pin "2") (pinfunction "2_2") (pintype "passive"))
      (node (ref "C20") (pin "2") (pinfunction "2_2") (pintype "passive"))
      (node (ref "C21") (pin "2") (pinfunction "2_2") (pintype "passive"))
      (node (ref "C22") (pin "2") (pinfunction "2_2") (pintype "passive"))
      (node (ref "C3") (pin "2") (pinfunction "2_2") (pintype "passive"))
      (node (ref "C4") (pin "2") (pinfunction "2_2") (pintype "passive"))
      (node (ref "C5") (pin "2") (pinfunction "2_2") (pintype "passive"))
      (node (ref "C6") (pin "2") (pinfunction "2_2") (pintype "passive"))
      (node (ref "C8") (pin "2") (pinfunction "2_2") (pintype "passive"))
      (node (ref "C9") (pin "2") (pinfunction "2_2") (pintype "passive"))
      (node (ref "D2") (pin "1") (pinfunction "C_1") (pintype "passive"))
      (node (ref "D4") (pin "1") (pinfunction "C_1") (pintype "passive"))
      (node (ref "F2") (pin "2") (pinfunction "2_2") (pintype "passive"))
      (node (ref "J2") (pin "1") (pinfunction "1_1") (pintype "passive"))
      (node (ref "J2") (pin "2") (pinfunction "2_2") (pintype "passive"))
      (node (ref "K100") (pin "3") (pinfunction "CONTACT1_3") (pintype "bidirectional"))
      (node (ref "R107") (pin "1") (pinfunction "1_1") (pintype "passive"))
      (node (ref "R108") (pin "1") (pinfunction "1_1") (pintype "passive"))
      (node (ref "R111") (pin "2") (pinfunction "2_2") (pintype "passive"))
      (node (ref "R112") (pin "1") (pinfunction "1_1") (pintype "passive"))
      (node (ref "R16") (pin "1") (pinfunction "1_1") (pintype "passive"))
      (node (ref "R17") (pin "1") (pinfunction "1_1") (pintype "passive"))
      (node (ref "R18") (pin "1") (pinfunction "1_1") (pintype "passive"))
      (node (ref "R19") (pin "1") (pinfunction "1_1") (pintype "passive"))
      (node (ref "TP7") (pin "1") (pinfunction "P$1_1") (pintype "passive"))
      (node (ref "U1") (pin "16") (pinfunction "GND_16") (pintype "power_in"))
      (node (ref "U1") (pin "6") (pinfunction "VPRG2_6") (pintype "input"))
      (node (ref "U1") (pin "8") (pinfunction "GND_8") (pintype "power_in"))
      (node (ref "U103") (pin "5") (pinfunction "-IN_5") (pintype "power_in"))
      (node (ref "U2") (pin "4") (pinfunction "GND1_4") (pintype "power_in"))
      (node (ref "U3") (pin "4") (pinfunction "GND1_4") (pintype "power_in"))
    )
    (net (code "64") (name "TS-UNFUSED") (class "Default")
      (node (ref "F2") (pin "1") (pinfunction "1_1") (pintype "passive"))
      (node (ref "J2") (pin "5") (pinfunction "5_5") (pintype "passive"))
      (node (ref "R13") (pin "1") (pinfunction "1_1") (pintype "passive"))
      (node (ref "R8") (pin "1") (pinfunction "1_1") (pintype "passive"))
      (node (ref "TP11") (pin "1") (pinfunction "P$1_1") (pintype "passive"))
    )
    (net (code "65") (name "TSMP+") (class "Default")
      (node (ref "J3") (pin "3") (pinfunction "3_3") (pintype "passive"))
      (node (ref "R7") (pin "2") (pinfunction "2_2") (pintype "passive"))
      (node (ref "TP4") (pin "1") (pinfunction "P$1_1") (pintype "passive"))
    )
    (net (code "66") (name "TSMP-") (class "Default")
      (node (ref "J2") (pin "4") (pinfunction "4_4") (pintype "passive"))
      (node (ref "R8") (pin "2") (pinfunction "2_2") (pintype "passive"))
      (node (ref "TP5") (pin "1") (pinfunction "P$1_1") (pintype "passive"))
    )
    (net (code "67") (name "TS_DO") (class "Default")
      (node (ref "R15") (pin "1") (pinfunction "1_1") (pintype "passive"))
      (node (ref "R17") (pin "2") (pinfunction "2_2") (pintype "passive"))
      (node (ref "R19") (pin "2") (pinfunction "2_2") (pintype "passive"))
      (node (ref "R21") (pin "1") (pinfunction "1_1") (pintype "passive"))
      (node (ref "TP12") (pin "1") (pinfunction "P$1_1") (pintype "passive"))
    )
    (net (code "68") (name "unconnected-(U1-FBO-Pad5)") (class "Default")
      (node (ref "U1") (pin "5") (pinfunction "FBO_5") (pintype "output"))
    )
  )
)
